# eos26_motherboard_basic.net
KiCad netlist of a schematic drawn in Altium Designer
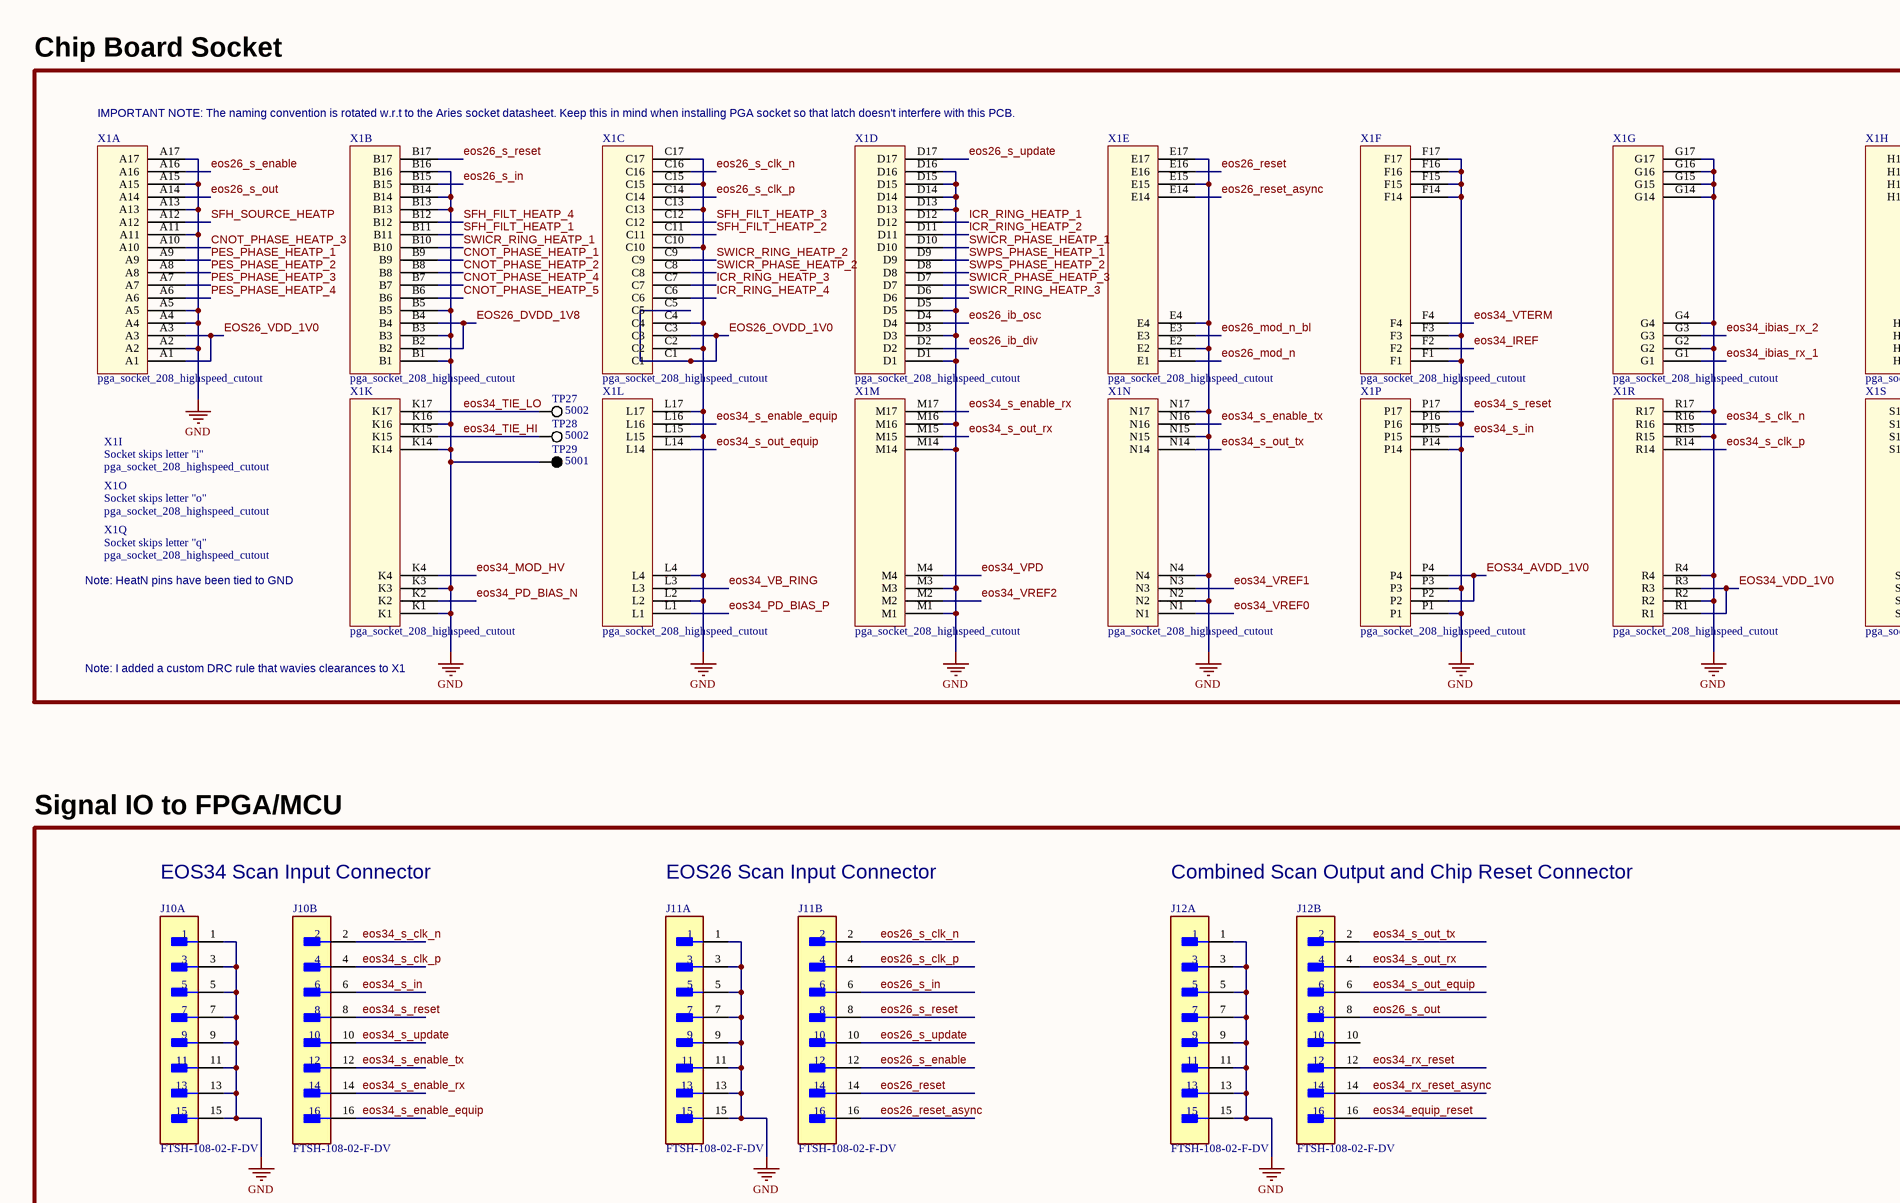
[diagram p0: eos26_motherboard_basic.SchDoc, top left]
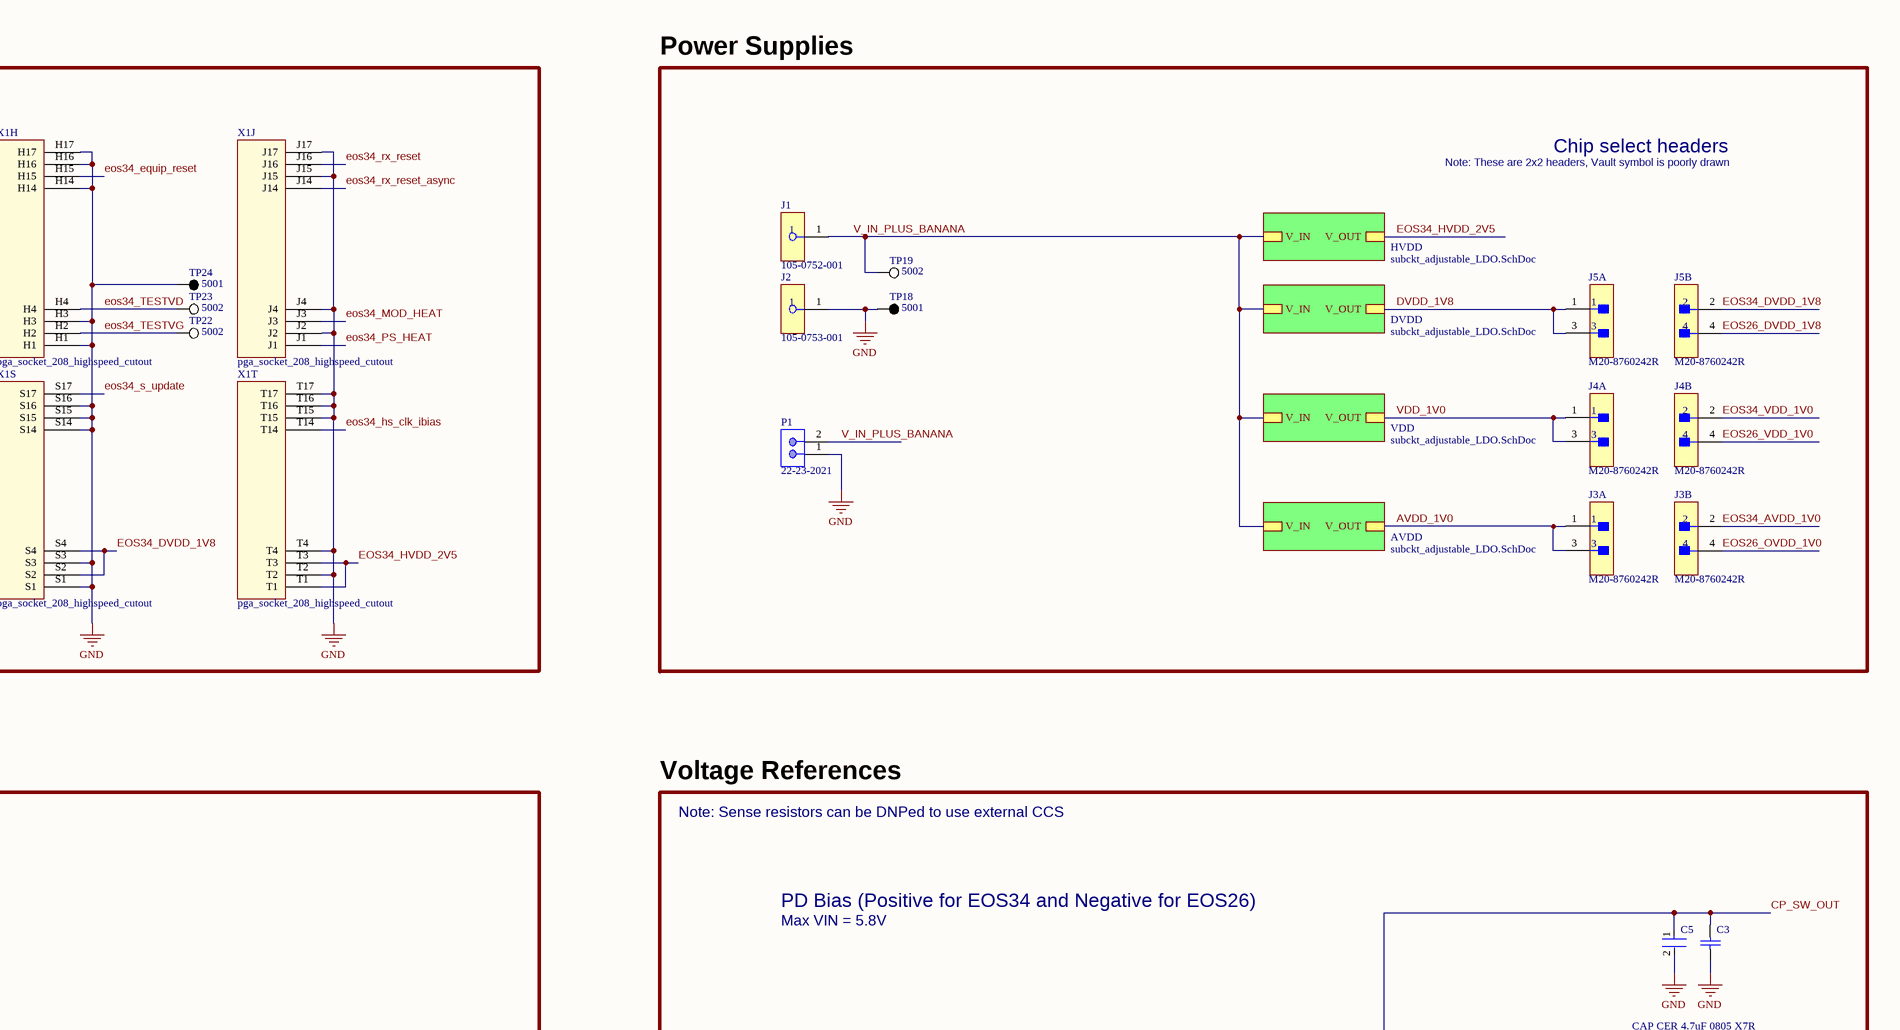
[diagram p1: eos26_motherboard_basic.SchDoc, top right]
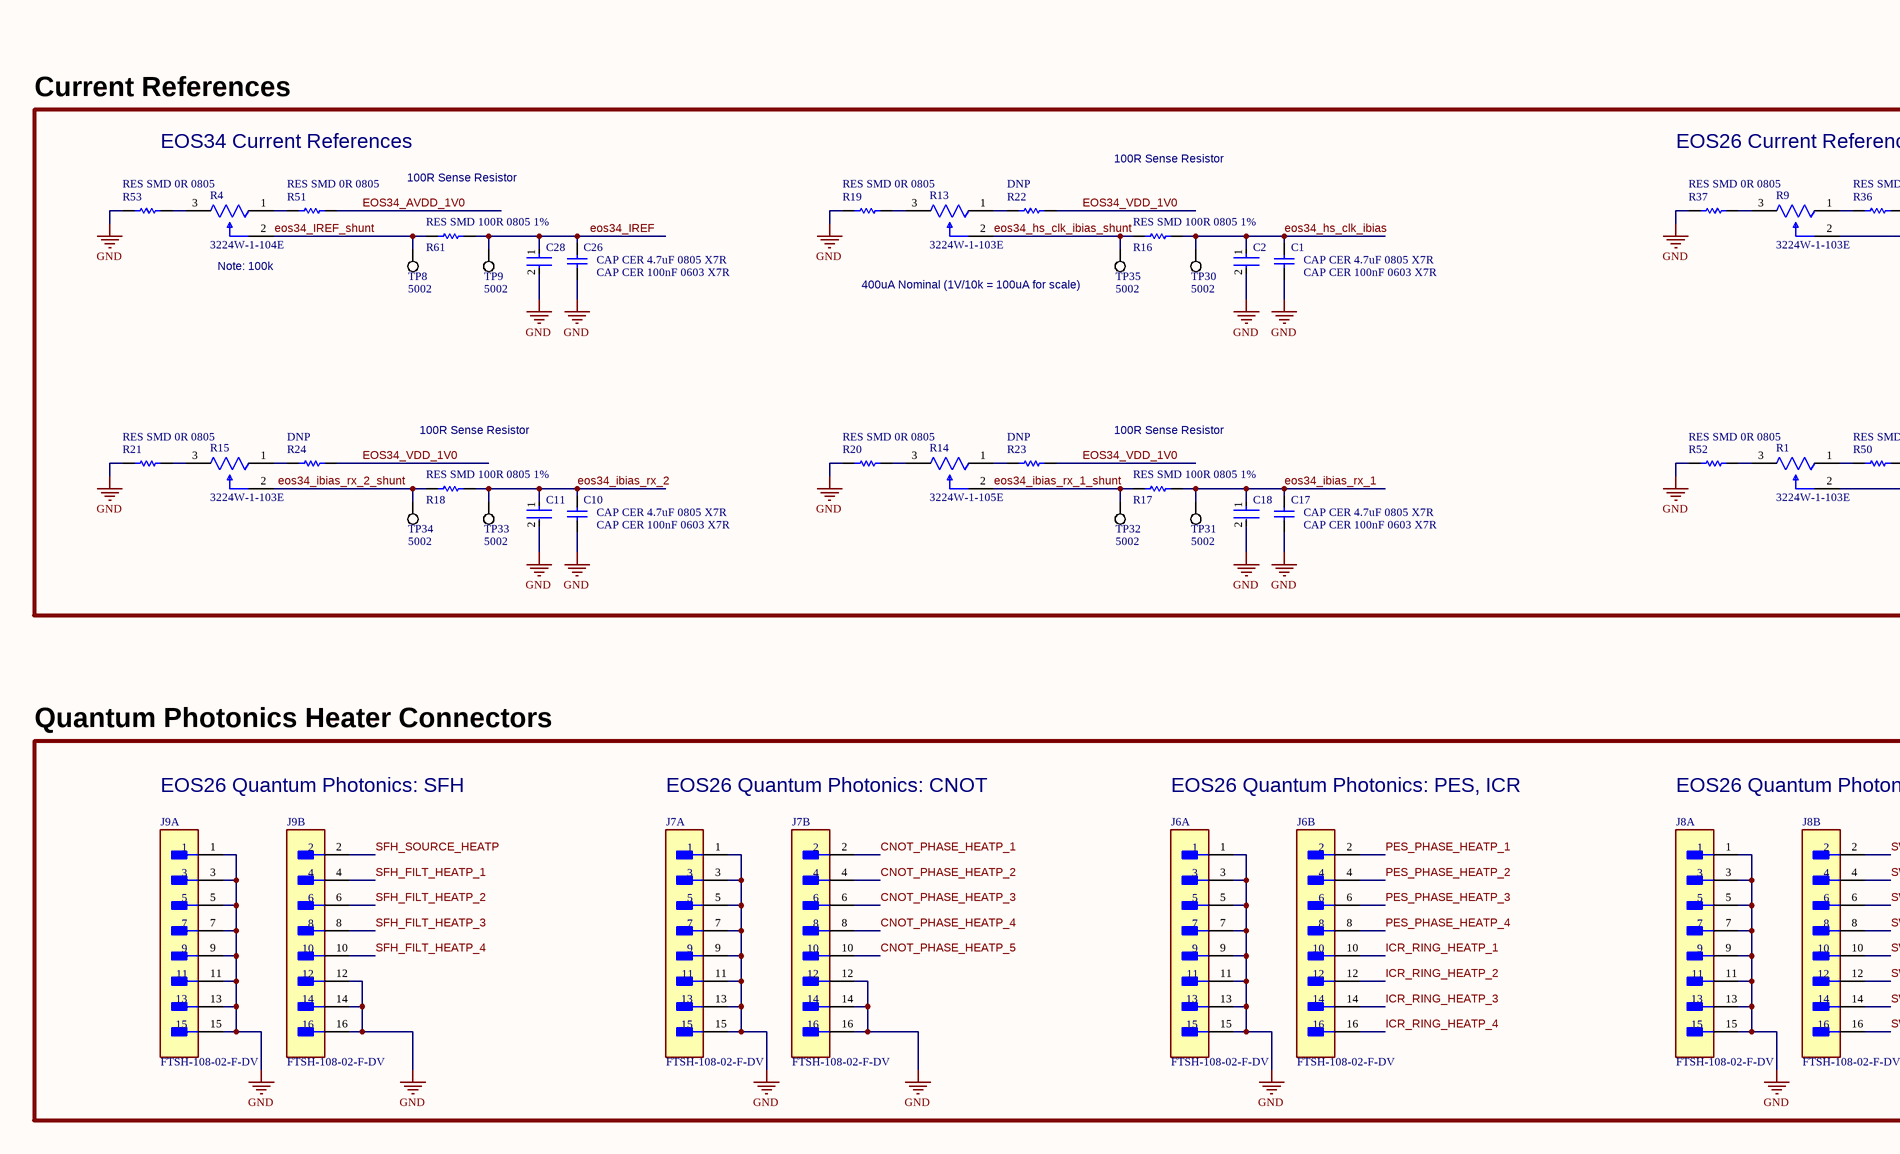
[diagram p2: eos26_motherboard_basic.SchDoc, bottom left]
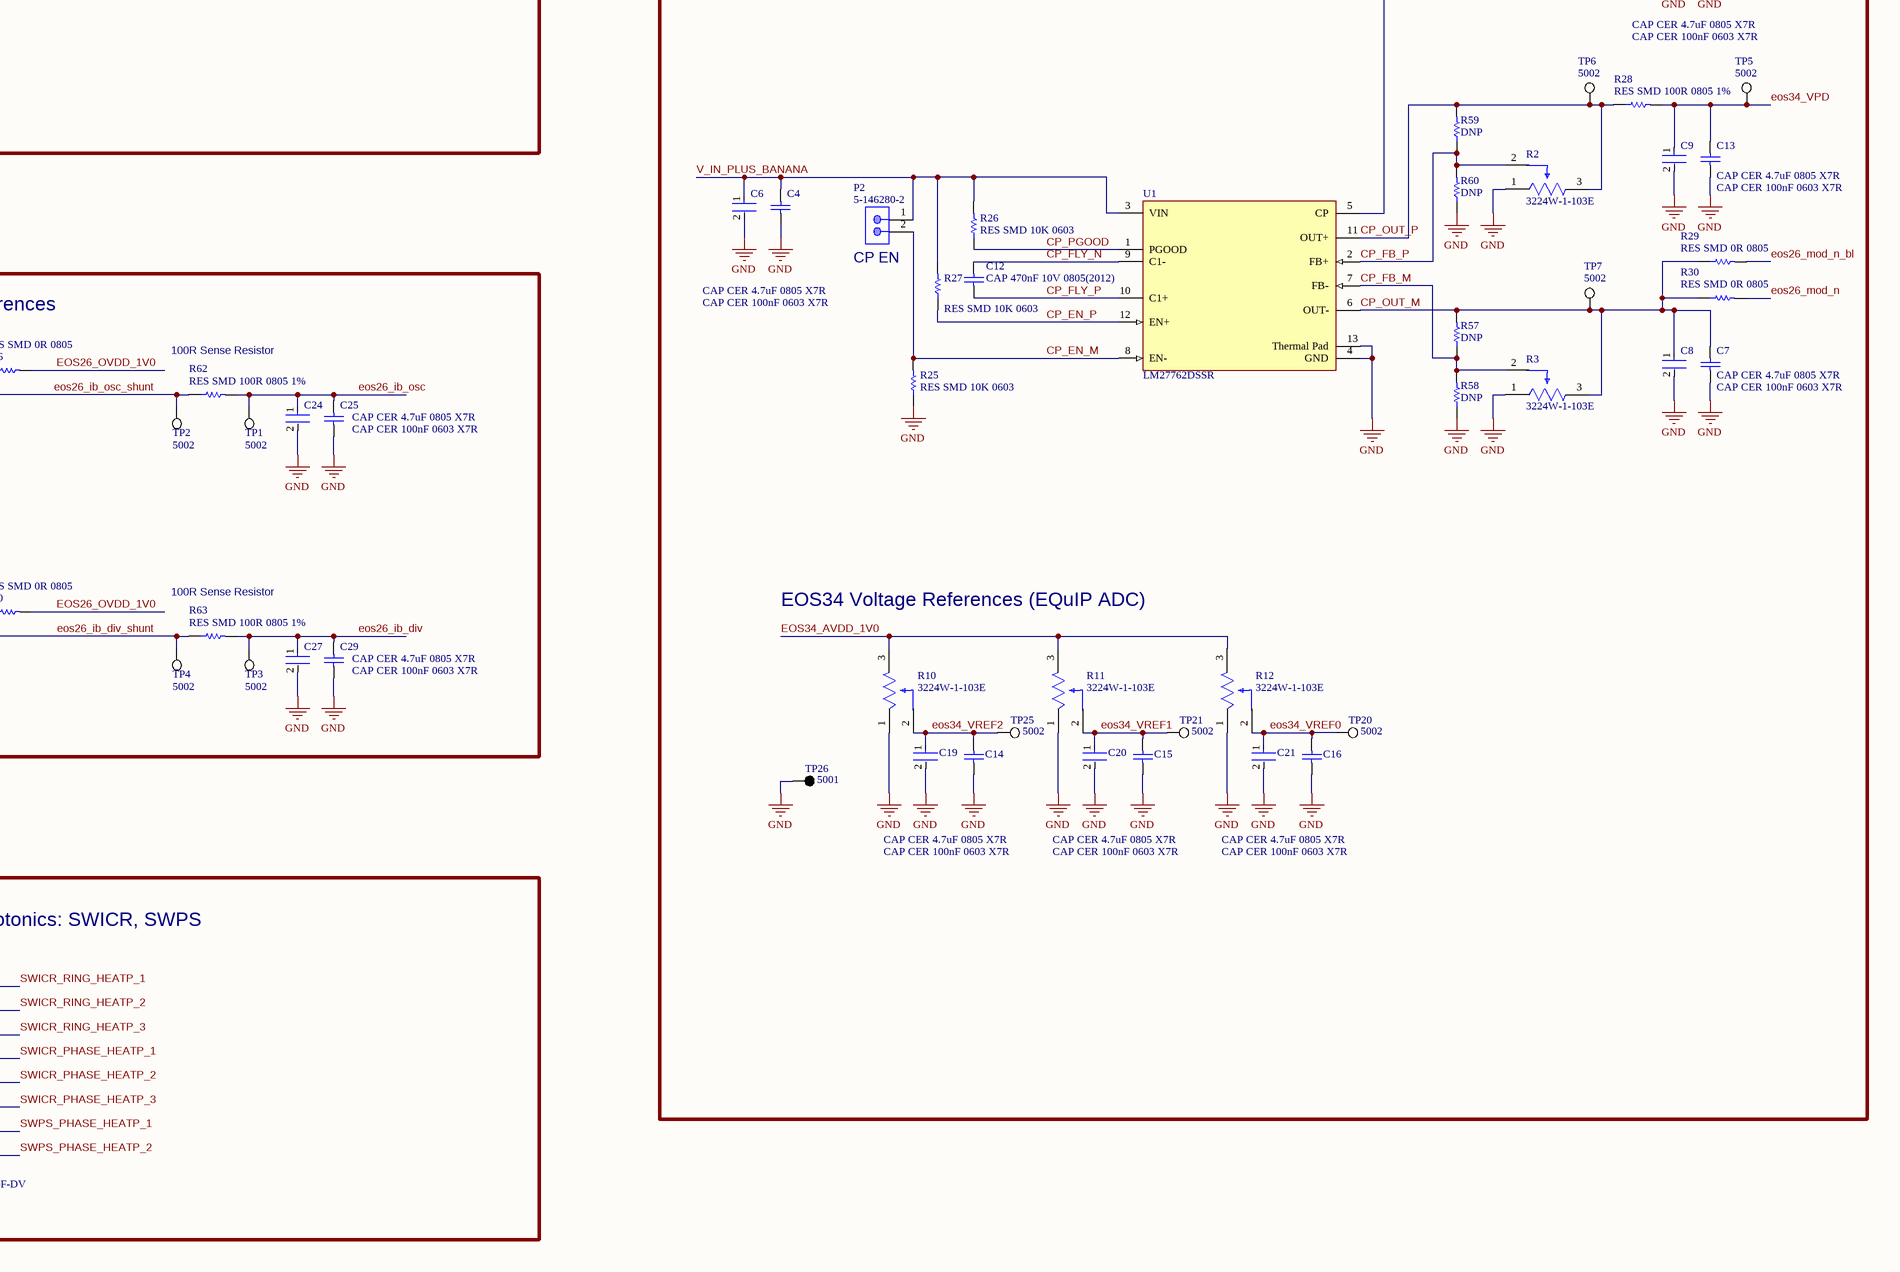
[diagram p3: eos26_motherboard_basic.SchDoc, bottom right]

(export (version "E")
  (design (tool "Eeschema 10.0.6"))
  (components
    (comp (ref "C1")
      (value "CAP CER 4.7uF 0805 X7R")
      (footprint "CAPC2013X140X50NL20T25")
      (fields
        (field (name "PART NUMBER") "0805ZC475KAT2A")
        (field (name "MANUFACTURER") "AVX Interconnect / Elco")
      )
      (libsource (lib "Altium Content Vault") (part "CAP"))
    )
    (comp (ref "C2")
      (value "CAP CER 100nF 0603 X7R")
      (footprint "FP-CC0603-DA-MFG")
      (description "CAP CER 0.1UF 16V X7R 0603")
      (fields
        (field (name "OCTOPART") "https://octopart.com/cc0603krx7r7bb104-yageo-192941")
        (field (name "TOLERANCE") "0.1")
      )
      (libsource (lib "Altium Content Vault") (part "11868f565c42a9108669ba33697ecf6"))
    )
    (comp (ref "C3")
      (value "CAP CER 4.7uF 0805 X7R")
      (footprint "CAPC2013X140X50NL20T25")
      (fields
        (field (name "PART NUMBER") "0805ZC475KAT2A")
        (field (name "MANUFACTURER") "AVX Interconnect / Elco")
      )
      (libsource (lib "Altium Content Vault") (part "CAP"))
    )
    (comp (ref "C4")
      (value "CAP CER 4.7uF 0805 X7R")
      (footprint "CAPC2013X140X50NL20T25")
      (fields
        (field (name "PART NUMBER") "0805ZC475KAT2A")
        (field (name "MANUFACTURER") "AVX Interconnect / Elco")
      )
      (libsource (lib "Altium Content Vault") (part "CAP"))
    )
    (comp (ref "C5")
      (value "CAP CER 100nF 0603 X7R")
      (footprint "FP-CC0603-DA-MFG")
      (description "CAP CER 0.1UF 16V X7R 0603")
      (fields
        (field (name "OCTOPART") "https://octopart.com/cc0603krx7r7bb104-yageo-192941")
        (field (name "TOLERANCE") "0.1")
      )
      (libsource (lib "Altium Content Vault") (part "11868f565c42a9108669ba33697ecf6"))
    )
    (comp (ref "C6")
      (value "CAP CER 100nF 0603 X7R")
      (footprint "FP-CC0603-DA-MFG")
      (description "CAP CER 0.1UF 16V X7R 0603")
      (fields
        (field (name "OCTOPART") "https://octopart.com/cc0603krx7r7bb104-yageo-192941")
        (field (name "TOLERANCE") "0.1")
      )
      (libsource (lib "Altium Content Vault") (part "11868f565c42a9108669ba33697ecf6"))
    )
    (comp (ref "C7")
      (value "CAP CER 4.7uF 0805 X7R")
      (footprint "CAPC2013X140X50NL20T25")
      (fields
        (field (name "PART NUMBER") "0805ZC475KAT2A")
        (field (name "MANUFACTURER") "AVX Interconnect / Elco")
      )
      (libsource (lib "Altium Content Vault") (part "CAP"))
    )
    (comp (ref "C8")
      (value "CAP CER 100nF 0603 X7R")
      (footprint "FP-CC0603-DA-MFG")
      (description "CAP CER 0.1UF 16V X7R 0603")
      (fields
        (field (name "OCTOPART") "https://octopart.com/cc0603krx7r7bb104-yageo-192941")
        (field (name "TOLERANCE") "0.1")
      )
      (libsource (lib "Altium Content Vault") (part "11868f565c42a9108669ba33697ecf6"))
    )
    (comp (ref "C9")
      (value "CAP CER 100nF 0603 X7R")
      (footprint "FP-CC0603-DA-MFG")
      (description "CAP CER 0.1UF 16V X7R 0603")
      (fields
        (field (name "OCTOPART") "https://octopart.com/cc0603krx7r7bb104-yageo-192941")
        (field (name "TOLERANCE") "0.1")
      )
      (libsource (lib "Altium Content Vault") (part "11868f565c42a9108669ba33697ecf6"))
    )
    (comp (ref "C10")
      (value "CAP CER 4.7uF 0805 X7R")
      (footprint "CAPC2013X140X50NL20T25")
      (fields
        (field (name "PART NUMBER") "0805ZC475KAT2A")
        (field (name "MANUFACTURER") "AVX Interconnect / Elco")
      )
      (libsource (lib "Altium Content Vault") (part "CAP"))
    )
    (comp (ref "C11")
      (value "CAP CER 100nF 0603 X7R")
      (footprint "FP-CC0603-DA-MFG")
      (description "CAP CER 0.1UF 16V X7R 0603")
      (fields
        (field (name "OCTOPART") "https://octopart.com/cc0603krx7r7bb104-yageo-192941")
        (field (name "TOLERANCE") "0.1")
      )
      (libsource (lib "Altium Content Vault") (part "11868f565c42a9108669ba33697ecf6"))
    )
    (comp (ref "C12")
      (value "CAP 470nF 10V 0805(2012)")
      (footprint "CAPC0805(2012)145_M")
      (description "CAP 470nF 10V ±5% 0805 (2012 Metric) Thickness 1.45mm SMD")
      (fields (field (name "TOLERANCE") "Â±5%"))
      (libsource (lib "Altium Content Vault") (part "CAP"))
    )
    (comp (ref "C13")
      (value "CAP CER 4.7uF 0805 X7R")
      (footprint "CAPC2013X140X50NL20T25")
      (fields
        (field (name "PART NUMBER") "0805ZC475KAT2A")
        (field (name "MANUFACTURER") "AVX Interconnect / Elco")
      )
      (libsource (lib "Altium Content Vault") (part "CAP"))
    )
    (comp (ref "C14")
      (value "CAP CER 4.7uF 0805 X7R")
      (footprint "CAPC2013X140X50NL20T25")
      (fields
        (field (name "PART NUMBER") "0805ZC475KAT2A")
        (field (name "MANUFACTURER") "AVX Interconnect / Elco")
      )
      (libsource (lib "Altium Content Vault") (part "CAP"))
    )
    (comp (ref "C15")
      (value "CAP CER 4.7uF 0805 X7R")
      (footprint "CAPC2013X140X50NL20T25")
      (fields
        (field (name "PART NUMBER") "0805ZC475KAT2A")
        (field (name "MANUFACTURER") "AVX Interconnect / Elco")
      )
      (libsource (lib "Altium Content Vault") (part "CAP"))
    )
    (comp (ref "C16")
      (value "CAP CER 4.7uF 0805 X7R")
      (footprint "CAPC2013X140X50NL20T25")
      (fields
        (field (name "PART NUMBER") "0805ZC475KAT2A")
        (field (name "MANUFACTURER") "AVX Interconnect / Elco")
      )
      (libsource (lib "Altium Content Vault") (part "CAP"))
    )
    (comp (ref "C17")
      (value "CAP CER 4.7uF 0805 X7R")
      (footprint "CAPC2013X140X50NL20T25")
      (fields
        (field (name "PART NUMBER") "0805ZC475KAT2A")
        (field (name "MANUFACTURER") "AVX Interconnect / Elco")
      )
      (libsource (lib "Altium Content Vault") (part "CAP"))
    )
    (comp (ref "C18")
      (value "CAP CER 100nF 0603 X7R")
      (footprint "FP-CC0603-DA-MFG")
      (description "CAP CER 0.1UF 16V X7R 0603")
      (fields
        (field (name "OCTOPART") "https://octopart.com/cc0603krx7r7bb104-yageo-192941")
        (field (name "TOLERANCE") "0.1")
      )
      (libsource (lib "Altium Content Vault") (part "11868f565c42a9108669ba33697ecf6"))
    )
    (comp (ref "C19")
      (value "CAP CER 100nF 0603 X7R")
      (footprint "FP-CC0603-DA-MFG")
      (description "CAP CER 0.1UF 16V X7R 0603")
      (fields
        (field (name "OCTOPART") "https://octopart.com/cc0603krx7r7bb104-yageo-192941")
        (field (name "TOLERANCE") "0.1")
      )
      (libsource (lib "Altium Content Vault") (part "11868f565c42a9108669ba33697ecf6"))
    )
    (comp (ref "C20")
      (value "CAP CER 100nF 0603 X7R")
      (footprint "FP-CC0603-DA-MFG")
      (description "CAP CER 0.1UF 16V X7R 0603")
      (fields
        (field (name "OCTOPART") "https://octopart.com/cc0603krx7r7bb104-yageo-192941")
        (field (name "TOLERANCE") "0.1")
      )
      (libsource (lib "Altium Content Vault") (part "11868f565c42a9108669ba33697ecf6"))
    )
    (comp (ref "C21")
      (value "CAP CER 100nF 0603 X7R")
      (footprint "FP-CC0603-DA-MFG")
      (description "CAP CER 0.1UF 16V X7R 0603")
      (fields
        (field (name "OCTOPART") "https://octopart.com/cc0603krx7r7bb104-yageo-192941")
        (field (name "TOLERANCE") "0.1")
      )
      (libsource (lib "Altium Content Vault") (part "11868f565c42a9108669ba33697ecf6"))
    )
    (comp (ref "C24")
      (value "CAP CER 100nF 0603 X7R")
      (footprint "FP-CC0603-DA-MFG")
      (description "CAP CER 0.1UF 16V X7R 0603")
      (fields
        (field (name "OCTOPART") "https://octopart.com/cc0603krx7r7bb104-yageo-192941")
        (field (name "TOLERANCE") "0.1")
      )
      (libsource (lib "Altium Content Vault") (part "11868f565c42a9108669ba33697ecf6"))
    )
    (comp (ref "C25")
      (value "CAP CER 4.7uF 0805 X7R")
      (footprint "CAPC2013X140X50NL20T25")
      (fields
        (field (name "PART NUMBER") "0805ZC475KAT2A")
        (field (name "MANUFACTURER") "AVX Interconnect / Elco")
      )
      (libsource (lib "Altium Content Vault") (part "CAP"))
    )
    (comp (ref "C26")
      (value "CAP CER 4.7uF 0805 X7R")
      (footprint "CAPC2013X140X50NL20T25")
      (fields
        (field (name "PART NUMBER") "0805ZC475KAT2A")
        (field (name "MANUFACTURER") "AVX Interconnect / Elco")
      )
      (libsource (lib "Altium Content Vault") (part "CAP"))
    )
    (comp (ref "C27")
      (value "CAP CER 100nF 0603 X7R")
      (footprint "FP-CC0603-DA-MFG")
      (description "CAP CER 0.1UF 16V X7R 0603")
      (fields
        (field (name "OCTOPART") "https://octopart.com/cc0603krx7r7bb104-yageo-192941")
        (field (name "TOLERANCE") "0.1")
      )
      (libsource (lib "Altium Content Vault") (part "11868f565c42a9108669ba33697ecf6"))
    )
    (comp (ref "C28")
      (value "CAP CER 100nF 0603 X7R")
      (footprint "FP-CC0603-DA-MFG")
      (description "CAP CER 0.1UF 16V X7R 0603")
      (fields
        (field (name "OCTOPART") "https://octopart.com/cc0603krx7r7bb104-yageo-192941")
        (field (name "TOLERANCE") "0.1")
      )
      (libsource (lib "Altium Content Vault") (part "11868f565c42a9108669ba33697ecf6"))
    )
    (comp (ref "C29")
      (value "CAP CER 4.7uF 0805 X7R")
      (footprint "CAPC2013X140X50NL20T25")
      (fields
        (field (name "PART NUMBER") "0805ZC475KAT2A")
        (field (name "MANUFACTURER") "AVX Interconnect / Elco")
      )
      (libsource (lib "Altium Content Vault") (part "CAP"))
    )
    (comp (ref "J1")
      (value "105-0752-001")
      (footprint "FP-105-0751-001-MFG")
      (description "CONN TIP JACK SOLDER WHITE")
      (fields
        (field (name "MANUFACTURER") "Cinch Connectivity")
        (field (name "OCTOPART") "https://octopart.com/105-0751-001-cinch+connectivity+solutions-51372833")
      )
      (libsource (lib "Altium Content Vault") (part "98815daf2f2c152b0c43f5ab9800df6"))
    )
    (comp (ref "J2")
      (value "105-0753-001")
      (footprint "FP-105-0751-001-MFG")
      (description "CONN TIP JACK SOLDER WHITE")
      (fields
        (field (name "MANUFACTURER") "Cinch Connectivity")
        (field (name "OCTOPART") "https://octopart.com/105-0751-001-cinch+connectivity+solutions-51372833")
      )
      (libsource (lib "Altium Content Vault") (part "98815daf2f2c152b0c43f5ab9800df6"))
    )
    (comp (ref "J3")
      (value "M20-8760242R")
      (footprint "FP-M20-8760242R-MFG")
      (description "CONN HEADER SMD 4POS 2.54MM")
      (libsource (lib "Altium Content Vault") (part "1621473add15499e993d6bbd36d0f06"))
    )
    (comp (ref "J4")
      (value "M20-8760242R")
      (footprint "FP-M20-8760242R-MFG")
      (description "CONN HEADER SMD 4POS 2.54MM")
      (libsource (lib "Altium Content Vault") (part "1621473add15499e993d6bbd36d0f06"))
    )
    (comp (ref "J5")
      (value "M20-8760242R")
      (footprint "FP-M20-8760242R-MFG")
      (description "CONN HEADER SMD 4POS 2.54MM")
      (libsource (lib "Altium Content Vault") (part "1621473add15499e993d6bbd36d0f06"))
    )
    (comp (ref "J6")
      (value "FTSH-108-02-F-DV")
      (footprint "LIBRARYSOURCE=Vault¦VAULTGUID=B7D15EC3-160A-466F-A46C-7801FE6295A7¦REVISIONGUID=4386816A-B426-492F-A73C-09950B70C106¦FOOTPRINT=FP-FTSH-108-02-F-DV")
      (description "CONN HEADER SMD 16POS 1.27MM")
      (fields
        (field (name "OCTOPART") "https://octopart.com/ftsh-108-02-f-dv-samtec-10605893")
        (field (name "MANUFACTURER") "Samtec")
      )
      (libsource (lib "SMT_header_FTSH") (part "FP-FTSH-108-02-F-DV"))
    )
    (comp (ref "J7")
      (value "FTSH-108-02-F-DV")
      (footprint "LIBRARYSOURCE=Vault¦VAULTGUID=B7D15EC3-160A-466F-A46C-7801FE6295A7¦REVISIONGUID=4386816A-B426-492F-A73C-09950B70C106¦FOOTPRINT=FP-FTSH-108-02-F-DV")
      (description "CONN HEADER SMD 16POS 1.27MM")
      (fields
        (field (name "OCTOPART") "https://octopart.com/ftsh-108-02-f-dv-samtec-10605893")
        (field (name "MANUFACTURER") "Samtec")
      )
      (libsource (lib "SMT_header_FTSH") (part "FP-FTSH-108-02-F-DV"))
    )
    (comp (ref "J8")
      (value "FTSH-108-02-F-DV")
      (footprint "LIBRARYSOURCE=Vault¦VAULTGUID=B7D15EC3-160A-466F-A46C-7801FE6295A7¦REVISIONGUID=4386816A-B426-492F-A73C-09950B70C106¦FOOTPRINT=FP-FTSH-108-02-F-DV")
      (description "CONN HEADER SMD 16POS 1.27MM")
      (fields
        (field (name "OCTOPART") "https://octopart.com/ftsh-108-02-f-dv-samtec-10605893")
        (field (name "MANUFACTURER") "Samtec")
      )
      (libsource (lib "SMT_header_FTSH") (part "FP-FTSH-108-02-F-DV"))
    )
    (comp (ref "J9")
      (value "FTSH-108-02-F-DV")
      (footprint "LIBRARYSOURCE=Vault¦VAULTGUID=B7D15EC3-160A-466F-A46C-7801FE6295A7¦REVISIONGUID=4386816A-B426-492F-A73C-09950B70C106¦FOOTPRINT=FP-FTSH-108-02-F-DV")
      (description "CONN HEADER SMD 16POS 1.27MM")
      (fields
        (field (name "OCTOPART") "https://octopart.com/ftsh-108-02-f-dv-samtec-10605893")
        (field (name "MANUFACTURER") "Samtec")
      )
      (libsource (lib "SMT_header_FTSH") (part "FP-FTSH-108-02-F-DV"))
    )
    (comp (ref "J10")
      (value "FTSH-108-02-F-DV")
      (footprint "LIBRARYSOURCE=Vault¦VAULTGUID=B7D15EC3-160A-466F-A46C-7801FE6295A7¦REVISIONGUID=4386816A-B426-492F-A73C-09950B70C106¦FOOTPRINT=FP-FTSH-108-02-F-DV")
      (description "CONN HEADER SMD 16POS 1.27MM")
      (fields
        (field (name "OCTOPART") "https://octopart.com/ftsh-108-02-f-dv-samtec-10605893")
        (field (name "MANUFACTURER") "Samtec")
      )
      (libsource (lib "SMT_header_FTSH") (part "FP-FTSH-108-02-F-DV"))
    )
    (comp (ref "J11")
      (value "FTSH-108-02-F-DV")
      (footprint "LIBRARYSOURCE=Vault¦VAULTGUID=B7D15EC3-160A-466F-A46C-7801FE6295A7¦REVISIONGUID=4386816A-B426-492F-A73C-09950B70C106¦FOOTPRINT=FP-FTSH-108-02-F-DV")
      (description "CONN HEADER SMD 16POS 1.27MM")
      (fields
        (field (name "OCTOPART") "https://octopart.com/ftsh-108-02-f-dv-samtec-10605893")
        (field (name "MANUFACTURER") "Samtec")
      )
      (libsource (lib "SMT_header_FTSH") (part "FP-FTSH-108-02-F-DV"))
    )
    (comp (ref "J12")
      (value "FTSH-108-02-F-DV")
      (footprint "LIBRARYSOURCE=Vault¦VAULTGUID=B7D15EC3-160A-466F-A46C-7801FE6295A7¦REVISIONGUID=4386816A-B426-492F-A73C-09950B70C106¦FOOTPRINT=FP-FTSH-108-02-F-DV")
      (description "CONN HEADER SMD 16POS 1.27MM")
      (fields
        (field (name "OCTOPART") "https://octopart.com/ftsh-108-02-f-dv-samtec-10605893")
        (field (name "MANUFACTURER") "Samtec")
      )
      (libsource (lib "SMT_header_FTSH") (part "FP-FTSH-108-02-F-DV"))
    )
    (comp (ref "P1")
      (value "22-23-2021")
      (footprint "MOLX-22-23-2021_V")
      (libsource (lib "Altium Content Vault") (part "CN-1P-M-R2"))
    )
    (comp (ref "P2")
      (value "5-146280-2")
      (footprint "TECO-5-146280-2_V")
      (fields (field (name "MANUFACTURER") "TE Connectivity"))
      (libsource (lib "") (part "CN-1P-M-R2_1"))
    )
    (comp (ref "R1")
      (value "3224W-1-103E")
      (footprint "FP-3224W-MFG")
      (description "TRIMMER 10K OHM 0.25W J LEAD TOP")
      (fields (field (name "TOLERANCE") "10%") (field (name "MANUFACTURER") "Bourns"))
      (libsource (lib "Altium Content Vault") (part "83d3d349ed884d1db45cec512f27eb6"))
    )
    (comp (ref "R2")
      (value "3224W-1-103E")
      (footprint "FP-3224W-MFG")
      (description "TRIMMER 10K OHM 0.25W J LEAD TOP")
      (fields (field (name "TOLERANCE") "10%") (field (name "MANUFACTURER") "Bourns"))
      (libsource (lib "Altium Content Vault") (part "83d3d349ed884d1db45cec512f27eb6"))
    )
    (comp (ref "R3")
      (value "3224W-1-103E")
      (footprint "FP-3224W-MFG")
      (description "TRIMMER 10K OHM 0.25W J LEAD TOP")
      (fields (field (name "TOLERANCE") "10%") (field (name "MANUFACTURER") "Bourns"))
      (libsource (lib "Altium Content Vault") (part "83d3d349ed884d1db45cec512f27eb6"))
    )
    (comp (ref "R4")
      (value "3224W-1-104E")
      (footprint "FP-3224W-MFG")
      (description "TRIMMER 10K OHM 0.25W J LEAD TOP")
      (fields (field (name "TOLERANCE") "10%") (field (name "MANUFACTURER") "Bourns"))
      (libsource (lib "Altium Content Vault") (part "83d3d349ed884d1db45cec512f27eb6"))
    )
    (comp (ref "R9")
      (value "3224W-1-103E")
      (footprint "FP-3224W-MFG")
      (description "TRIMMER 10K OHM 0.25W J LEAD TOP")
      (fields (field (name "TOLERANCE") "10%") (field (name "MANUFACTURER") "Bourns"))
      (libsource (lib "Altium Content Vault") (part "83d3d349ed884d1db45cec512f27eb6"))
    )
    (comp (ref "R10")
      (value "3224W-1-103E")
      (footprint "FP-3224W-MFG")
      (description "TRIMMER 10K OHM 0.25W J LEAD TOP")
      (fields (field (name "TOLERANCE") "10%") (field (name "MANUFACTURER") "Bourns"))
      (libsource (lib "Altium Content Vault") (part "83d3d349ed884d1db45cec512f27eb6"))
    )
    (comp (ref "R11")
      (value "3224W-1-103E")
      (footprint "FP-3224W-MFG")
      (description "TRIMMER 10K OHM 0.25W J LEAD TOP")
      (fields (field (name "TOLERANCE") "10%") (field (name "MANUFACTURER") "Bourns"))
      (libsource (lib "Altium Content Vault") (part "83d3d349ed884d1db45cec512f27eb6"))
    )
    (comp (ref "R12")
      (value "3224W-1-103E")
      (footprint "FP-3224W-MFG")
      (description "TRIMMER 10K OHM 0.25W J LEAD TOP")
      (fields (field (name "TOLERANCE") "10%") (field (name "MANUFACTURER") "Bourns"))
      (libsource (lib "Altium Content Vault") (part "83d3d349ed884d1db45cec512f27eb6"))
    )
    (comp (ref "R13")
      (value "3224W-1-103E")
      (footprint "FP-3224W-MFG")
      (description "TRIMMER 10K OHM 0.25W J LEAD TOP")
      (fields (field (name "TOLERANCE") "10%") (field (name "MANUFACTURER") "Bourns"))
      (libsource (lib "Altium Content Vault") (part "83d3d349ed884d1db45cec512f27eb6"))
    )
    (comp (ref "R14")
      (value "3224W-1-105E")
      (footprint "FP-3224W-MFG")
      (description "TRIMMER 10K OHM 0.25W J LEAD TOP")
      (fields (field (name "TOLERANCE") "10%") (field (name "MANUFACTURER") "Bourns"))
      (libsource (lib "Altium Content Vault") (part "83d3d349ed884d1db45cec512f27eb6"))
    )
    (comp (ref "R15")
      (value "3224W-1-103E")
      (footprint "FP-3224W-MFG")
      (description "TRIMMER 10K OHM 0.25W J LEAD TOP")
      (fields (field (name "TOLERANCE") "10%") (field (name "MANUFACTURER") "Bourns"))
      (libsource (lib "Altium Content Vault") (part "83d3d349ed884d1db45cec512f27eb6"))
    )
    (comp (ref "R16")
      (value "RES SMD 100R 0805 1%")
      (footprint "RESC2013X55X40NL15T20")
      (fields (field (name "MANUFACTURER") "Vishay Dale") (field (name "PART NUMBER") "TNPW0805100RBEEA"))
      (libsource (lib "Altium Content Vault") (part "RES"))
    )
    (comp (ref "R17")
      (value "RES SMD 100R 0805 1%")
      (footprint "RESC2013X55X40NL15T20")
      (fields (field (name "MANUFACTURER") "Vishay Dale") (field (name "PART NUMBER") "TNPW0805100RBEEA"))
      (libsource (lib "Altium Content Vault") (part "RES"))
    )
    (comp (ref "R18")
      (value "RES SMD 100R 0805 1%")
      (footprint "RESC2013X55X40NL15T20")
      (fields (field (name "MANUFACTURER") "Vishay Dale") (field (name "PART NUMBER") "TNPW0805100RBEEA"))
      (libsource (lib "Altium Content Vault") (part "RES"))
    )
    (comp (ref "R19")
      (value "RES SMD 0R 0805")
      (footprint "RESC2013X55X40NL15T20")
      (fields (field (name "MANUFACTURER") "Vishay Dale") (field (name "PART NUMBER") "TNPW0805100RBEEA"))
      (libsource (lib "Altium Content Vault") (part "RES"))
    )
    (comp (ref "R20")
      (value "RES SMD 0R 0805")
      (footprint "RESC2013X55X40NL15T20")
      (fields (field (name "MANUFACTURER") "Vishay Dale") (field (name "PART NUMBER") "TNPW0805100RBEEA"))
      (libsource (lib "Altium Content Vault") (part "RES"))
    )
    (comp (ref "R21")
      (value "RES SMD 0R 0805")
      (footprint "RESC2013X55X40NL15T20")
      (fields (field (name "MANUFACTURER") "Vishay Dale") (field (name "PART NUMBER") "TNPW0805100RBEEA"))
      (libsource (lib "Altium Content Vault") (part "RES"))
    )
    (comp (ref "R22")
      (value "DNP")
      (footprint "RESC2013X55X40NL15T20")
      (fields (field (name "MANUFACTURER") "Vishay Dale") (field (name "PART NUMBER") "TNPW0805100RBEEA"))
      (libsource (lib "Altium Content Vault") (part "RES"))
    )
    (comp (ref "R23")
      (value "DNP")
      (footprint "RESC2013X55X40NL15T20")
      (fields (field (name "MANUFACTURER") "Vishay Dale") (field (name "PART NUMBER") "TNPW0805100RBEEA"))
      (libsource (lib "Altium Content Vault") (part "RES"))
    )
    (comp (ref "R24")
      (value "DNP")
      (footprint "RESC2013X55X40NL15T20")
      (fields (field (name "MANUFACTURER") "Vishay Dale") (field (name "PART NUMBER") "TNPW0805100RBEEA"))
      (libsource (lib "Altium Content Vault") (part "RES"))
    )
    (comp (ref "R25")
      (value "RES SMD 10K 0603")
      (footprint "RESC1609X55X30LL15T15")
      (description "Chip Resistor, 10 KOhm, +/- 1%, 0.1 W, -55 to 155 degC, 0603 (1608 Metric), RoHS, Tape and Reel")
      (fields (field (name "TOLERANCE") "1%") (field (name "MANUFACTURER") "Panasonic"))
      (libsource (lib "Altium Content Vault") (part "RES-2"))
    )
    (comp (ref "R26")
      (value "RES SMD 10K 0603")
      (footprint "RESC1609X55X30LL15T15")
      (description "Chip Resistor, 10 KOhm, +/- 1%, 0.1 W, -55 to 155 degC, 0603 (1608 Metric), RoHS, Tape and Reel")
      (fields (field (name "TOLERANCE") "1%") (field (name "MANUFACTURER") "Panasonic"))
      (libsource (lib "Altium Content Vault") (part "RES-2"))
    )
    (comp (ref "R27")
      (value "RES SMD 10K 0603")
      (footprint "RESC1609X55X30LL15T15")
      (description "Chip Resistor, 10 KOhm, +/- 1%, 0.1 W, -55 to 155 degC, 0603 (1608 Metric), RoHS, Tape and Reel")
      (fields (field (name "TOLERANCE") "1%") (field (name "MANUFACTURER") "Panasonic"))
      (libsource (lib "Altium Content Vault") (part "RES-2"))
    )
    (comp (ref "R28")
      (value "RES SMD 100R 0805 1%")
      (footprint "RESC2013X55X40NL15T20")
      (fields (field (name "MANUFACTURER") "Vishay Dale") (field (name "PART NUMBER") "TNPW0805100RBEEA"))
      (libsource (lib "Altium Content Vault") (part "RES"))
    )
    (comp (ref "R29")
      (value "RES SMD 0R 0805")
      (footprint "RESC2013X55X40NL15T20")
      (fields (field (name "MANUFACTURER") "Vishay Dale") (field (name "PART NUMBER") "TNPW0805100RBEEA"))
      (libsource (lib "Altium Content Vault") (part "RES"))
    )
    (comp (ref "R30")
      (value "RES SMD 0R 0805")
      (footprint "RESC2013X55X40NL15T20")
      (fields (field (name "MANUFACTURER") "Vishay Dale") (field (name "PART NUMBER") "TNPW0805100RBEEA"))
      (libsource (lib "Altium Content Vault") (part "RES"))
    )
    (comp (ref "R36")
      (value "RES SMD 0R 0805")
      (footprint "RESC2013X55X40NL15T20")
      (fields (field (name "MANUFACTURER") "Vishay Dale") (field (name "PART NUMBER") "TNPW0805100RBEEA"))
      (libsource (lib "Altium Content Vault") (part "RES"))
    )
    (comp (ref "R37")
      (value "RES SMD 0R 0805")
      (footprint "RESC2013X55X40NL15T20")
      (fields (field (name "MANUFACTURER") "Vishay Dale") (field (name "PART NUMBER") "TNPW0805100RBEEA"))
      (libsource (lib "Altium Content Vault") (part "RES"))
    )
    (comp (ref "R50")
      (value "RES SMD 0R 0805")
      (footprint "RESC2013X55X40NL15T20")
      (fields (field (name "MANUFACTURER") "Vishay Dale") (field (name "PART NUMBER") "TNPW0805100RBEEA"))
      (libsource (lib "Altium Content Vault") (part "RES"))
    )
    (comp (ref "R51")
      (value "RES SMD 0R 0805")
      (footprint "RESC2013X55X40NL15T20")
      (fields (field (name "MANUFACTURER") "Vishay Dale") (field (name "PART NUMBER") "TNPW0805100RBEEA"))
      (libsource (lib "Altium Content Vault") (part "RES"))
    )
    (comp (ref "R52")
      (value "RES SMD 0R 0805")
      (footprint "RESC2013X55X40NL15T20")
      (fields (field (name "MANUFACTURER") "Vishay Dale") (field (name "PART NUMBER") "TNPW0805100RBEEA"))
      (libsource (lib "Altium Content Vault") (part "RES"))
    )
    (comp (ref "R53")
      (value "RES SMD 0R 0805")
      (footprint "RESC2013X55X40NL15T20")
      (fields (field (name "MANUFACTURER") "Vishay Dale") (field (name "PART NUMBER") "TNPW0805100RBEEA"))
      (libsource (lib "Altium Content Vault") (part "RES"))
    )
    (comp (ref "R57")
      (value "DNP")
      (footprint "RESC1608X55X30LL10T20_A")
      (description "Chip Resistor, 0 Ohm, +/- 5%, 100 mW, -55 to 155 degC, 0603 (1608 Metric), RoHS, Tape and Reel")
      (fields (field (name "TOLERANCE") "Jumper") (field (name "MANUFACTURER") "Rohm"))
      (libsource (lib "Altium Content Vault") (part "RES-2"))
    )
    (comp (ref "R58")
      (value "DNP")
      (footprint "RESC1608X55X30LL10T20_A")
      (description "Chip Resistor, 0 Ohm, +/- 5%, 100 mW, -55 to 155 degC, 0603 (1608 Metric), RoHS, Tape and Reel")
      (fields (field (name "TOLERANCE") "Jumper") (field (name "MANUFACTURER") "Rohm"))
      (libsource (lib "Altium Content Vault") (part "RES-2"))
    )
    (comp (ref "R59")
      (value "DNP")
      (footprint "RESC1608X55X30LL10T20_A")
      (description "Chip Resistor, 0 Ohm, +/- 5%, 100 mW, -55 to 155 degC, 0603 (1608 Metric), RoHS, Tape and Reel")
      (fields (field (name "TOLERANCE") "Jumper") (field (name "MANUFACTURER") "Rohm"))
      (libsource (lib "Altium Content Vault") (part "RES-2"))
    )
    (comp (ref "R60")
      (value "DNP")
      (footprint "RESC1608X55X30LL10T20_A")
      (description "Chip Resistor, 0 Ohm, +/- 5%, 100 mW, -55 to 155 degC, 0603 (1608 Metric), RoHS, Tape and Reel")
      (fields (field (name "TOLERANCE") "Jumper") (field (name "MANUFACTURER") "Rohm"))
      (libsource (lib "Altium Content Vault") (part "RES-2"))
    )
    (comp (ref "R61")
      (value "RES SMD 100R 0805 1%")
      (footprint "RESC2013X55X40NL15T20")
      (fields (field (name "MANUFACTURER") "Vishay Dale") (field (name "PART NUMBER") "TNPW0805100RBEEA"))
      (libsource (lib "Altium Content Vault") (part "RES"))
    )
    (comp (ref "R62")
      (value "RES SMD 100R 0805 1%")
      (footprint "RESC2013X55X40NL15T20")
      (fields (field (name "MANUFACTURER") "Vishay Dale") (field (name "PART NUMBER") "TNPW0805100RBEEA"))
      (libsource (lib "Altium Content Vault") (part "RES"))
    )
    (comp (ref "R63")
      (value "RES SMD 100R 0805 1%")
      (footprint "RESC2013X55X40NL15T20")
      (fields (field (name "MANUFACTURER") "Vishay Dale") (field (name "PART NUMBER") "TNPW0805100RBEEA"))
      (libsource (lib "Altium Content Vault") (part "RES"))
    )
    (comp (ref "TP1")
      (value "5002")
      (footprint "KSTN-5002")
      (description "Test Point, White, 1-Pin THD, RoHS, Bulk")
      (fields (field (name "MANUFACTURER") "KeystoneElectronics"))
      (libsource (lib "Altium Content Vault") (part "KSTN-TP-5002"))
    )
    (comp (ref "TP2")
      (value "5002")
      (footprint "KSTN-5002")
      (description "Test Point, White, 1-Pin THD, RoHS, Bulk")
      (fields (field (name "MANUFACTURER") "KeystoneElectronics"))
      (libsource (lib "Altium Content Vault") (part "KSTN-TP-5002"))
    )
    (comp (ref "TP3")
      (value "5002")
      (footprint "KSTN-5002")
      (description "Test Point, White, 1-Pin THD, RoHS, Bulk")
      (fields (field (name "MANUFACTURER") "KeystoneElectronics"))
      (libsource (lib "Altium Content Vault") (part "KSTN-TP-5002"))
    )
    (comp (ref "TP4")
      (value "5002")
      (footprint "KSTN-5002")
      (description "Test Point, White, 1-Pin THD, RoHS, Bulk")
      (fields (field (name "MANUFACTURER") "KeystoneElectronics"))
      (libsource (lib "Altium Content Vault") (part "KSTN-TP-5002"))
    )
    (comp (ref "TP5")
      (value "5002")
      (footprint "KSTN-5002")
      (description "Test Point, White, 1-Pin THD, RoHS, Bulk")
      (fields (field (name "MANUFACTURER") "KeystoneElectronics"))
      (libsource (lib "Altium Content Vault") (part "KSTN-TP-5002"))
    )
    (comp (ref "TP6")
      (value "5002")
      (footprint "KSTN-5002")
      (description "Test Point, White, 1-Pin THD, RoHS, Bulk")
      (fields (field (name "MANUFACTURER") "KeystoneElectronics"))
      (libsource (lib "Altium Content Vault") (part "KSTN-TP-5002"))
    )
    (comp (ref "TP7")
      (value "5002")
      (footprint "KSTN-5002")
      (description "Test Point, White, 1-Pin THD, RoHS, Bulk")
      (fields (field (name "MANUFACTURER") "KeystoneElectronics"))
      (libsource (lib "Altium Content Vault") (part "KSTN-TP-5002"))
    )
    (comp (ref "TP8")
      (value "5002")
      (footprint "KSTN-5002")
      (description "Test Point, White, 1-Pin THD, RoHS, Bulk")
      (fields (field (name "MANUFACTURER") "KeystoneElectronics"))
      (libsource (lib "Altium Content Vault") (part "KSTN-TP-5002"))
    )
    (comp (ref "TP9")
      (value "5002")
      (footprint "KSTN-5002")
      (description "Test Point, White, 1-Pin THD, RoHS, Bulk")
      (fields (field (name "MANUFACTURER") "KeystoneElectronics"))
      (libsource (lib "Altium Content Vault") (part "KSTN-TP-5002"))
    )
    (comp (ref "TP18")
      (value "5001")
      (footprint "KSTN-5001")
      (description "Test Point, Black, 1-Pin THD, RoHS, Bulk")
      (fields (field (name "MANUFACTURER") "Keystone"))
      (libsource (lib "Altium Content Vault") (part "KSTN-TP-5001"))
    )
    (comp (ref "TP19")
      (value "5002")
      (footprint "KSTN-5002")
      (description "Test Point, White, 1-Pin THD, RoHS, Bulk")
      (fields (field (name "MANUFACTURER") "KeystoneElectronics"))
      (libsource (lib "Altium Content Vault") (part "KSTN-TP-5002"))
    )
    (comp (ref "TP20")
      (value "5002")
      (footprint "KSTN-5002")
      (description "Test Point, White, 1-Pin THD, RoHS, Bulk")
      (fields (field (name "MANUFACTURER") "KeystoneElectronics"))
      (libsource (lib "Altium Content Vault") (part "KSTN-TP-5002"))
    )
    (comp (ref "TP21")
      (value "5002")
      (footprint "KSTN-5002")
      (description "Test Point, White, 1-Pin THD, RoHS, Bulk")
      (fields (field (name "MANUFACTURER") "KeystoneElectronics"))
      (libsource (lib "Altium Content Vault") (part "KSTN-TP-5002"))
    )
    (comp (ref "TP22")
      (value "5002")
      (footprint "KSTN-5002")
      (description "Test Point, White, 1-Pin THD, RoHS, Bulk")
      (fields (field (name "MANUFACTURER") "KeystoneElectronics"))
      (libsource (lib "Altium Content Vault") (part "KSTN-TP-5002"))
    )
    (comp (ref "TP23")
      (value "5002")
      (footprint "KSTN-5002")
      (description "Test Point, White, 1-Pin THD, RoHS, Bulk")
      (fields (field (name "MANUFACTURER") "KeystoneElectronics"))
      (libsource (lib "Altium Content Vault") (part "KSTN-TP-5002"))
    )
    (comp (ref "TP24")
      (value "5001")
      (footprint "KSTN-5001")
      (description "Test Point, Black, 1-Pin THD, RoHS, Bulk")
      (fields (field (name "MANUFACTURER") "Keystone"))
      (libsource (lib "Altium Content Vault") (part "KSTN-TP-5001"))
    )
    (comp (ref "TP25")
      (value "5002")
      (footprint "KSTN-5002")
      (description "Test Point, White, 1-Pin THD, RoHS, Bulk")
      (fields (field (name "MANUFACTURER") "KeystoneElectronics"))
      (libsource (lib "Altium Content Vault") (part "KSTN-TP-5002"))
    )
    (comp (ref "TP26")
      (value "5001")
      (footprint "KSTN-5001")
      (description "Test Point, Black, 1-Pin THD, RoHS, Bulk")
      (fields (field (name "MANUFACTURER") "Keystone"))
      (libsource (lib "Altium Content Vault") (part "KSTN-TP-5001"))
    )
    (comp (ref "TP27")
      (value "5002")
      (footprint "KSTN-5002")
      (description "Test Point, White, 1-Pin THD, RoHS, Bulk")
      (fields (field (name "MANUFACTURER") "KeystoneElectronics"))
      (libsource (lib "Altium Content Vault") (part "KSTN-TP-5002"))
    )
    (comp (ref "TP28")
      (value "5002")
      (footprint "KSTN-5002")
      (description "Test Point, White, 1-Pin THD, RoHS, Bulk")
      (fields (field (name "MANUFACTURER") "KeystoneElectronics"))
      (libsource (lib "Altium Content Vault") (part "KSTN-TP-5002"))
    )
    (comp (ref "TP29")
      (value "5001")
      (footprint "KSTN-5001")
      (description "Test Point, Black, 1-Pin THD, RoHS, Bulk")
      (fields (field (name "MANUFACTURER") "Keystone"))
      (libsource (lib "Altium Content Vault") (part "KSTN-TP-5001"))
    )
    (comp (ref "TP30")
      (value "5002")
      (footprint "KSTN-5002")
      (description "Test Point, White, 1-Pin THD, RoHS, Bulk")
      (fields (field (name "MANUFACTURER") "KeystoneElectronics"))
      (libsource (lib "Altium Content Vault") (part "KSTN-TP-5002"))
    )
    (comp (ref "TP31")
      (value "5002")
      (footprint "KSTN-5002")
      (description "Test Point, White, 1-Pin THD, RoHS, Bulk")
      (fields (field (name "MANUFACTURER") "KeystoneElectronics"))
      (libsource (lib "Altium Content Vault") (part "KSTN-TP-5002"))
    )
    (comp (ref "TP32")
      (value "5002")
      (footprint "KSTN-5002")
      (description "Test Point, White, 1-Pin THD, RoHS, Bulk")
      (fields (field (name "MANUFACTURER") "KeystoneElectronics"))
      (libsource (lib "Altium Content Vault") (part "KSTN-TP-5002"))
    )
    (comp (ref "TP33")
      (value "5002")
      (footprint "KSTN-5002")
      (description "Test Point, White, 1-Pin THD, RoHS, Bulk")
      (fields (field (name "MANUFACTURER") "KeystoneElectronics"))
      (libsource (lib "Altium Content Vault") (part "KSTN-TP-5002"))
    )
    (comp (ref "TP34")
      (value "5002")
      (footprint "KSTN-5002")
      (description "Test Point, White, 1-Pin THD, RoHS, Bulk")
      (fields (field (name "MANUFACTURER") "KeystoneElectronics"))
      (libsource (lib "Altium Content Vault") (part "KSTN-TP-5002"))
    )
    (comp (ref "TP35")
      (value "5002")
      (footprint "KSTN-5002")
      (description "Test Point, White, 1-Pin THD, RoHS, Bulk")
      (fields (field (name "MANUFACTURER") "KeystoneElectronics"))
      (libsource (lib "Altium Content Vault") (part "KSTN-TP-5002"))
    )
    (comp (ref "U1")
      (value "LM27762DSSR")
      (footprint "FP-DSS0012B-MFG")
      (description "IC REG CHARGE PUMP ADJ DL 12WSON")
      (libsource (lib "Altium Content Vault") (part "ab275a4f98ccada617dcf409ec46a20"))
    )
    (comp (ref "X1")
      (value "pga_socket_208_highspeed_cutout")
      (footprint "pga_socket_208pin_highspeed_cutout")
      (libsource (lib "pga_socket_square_208pin_17x17_minus_9x9") (part "pga_socket_208_highspeed_cutout"))
    )
  )
  (nets
    (net (code "1") (name "/AVDD_1V0") (class "Default")
      (node (ref "J3") (pin "1") (pinfunction "1_1") (pintype "passive"))
      (node (ref "J3") (pin "3") (pinfunction "3_3") (pintype "passive"))
    )
    (net (code "2") (name "/CNOT_PHASE_HEATP_1") (class "Default")
      (node (ref "J7") (pin "2") (pinfunction "2_2") (pintype "passive"))
      (node (ref "X1") (pin "B9") (pinfunction "B9_B9") (pintype "passive"))
    )
    (net (code "3") (name "/CNOT_PHASE_HEATP_2") (class "Default")
      (node (ref "J7") (pin "4") (pinfunction "4_4") (pintype "passive"))
      (node (ref "X1") (pin "B8") (pinfunction "B8_B8") (pintype "passive"))
    )
    (net (code "4") (name "/CNOT_PHASE_HEATP_3") (class "Default")
      (node (ref "J7") (pin "6") (pinfunction "6_6") (pintype "passive"))
      (node (ref "X1") (pin "A10") (pinfunction "A10_A10") (pintype "passive"))
    )
    (net (code "5") (name "/CNOT_PHASE_HEATP_4") (class "Default")
      (node (ref "J7") (pin "8") (pinfunction "8_8") (pintype "passive"))
      (node (ref "X1") (pin "B7") (pinfunction "B7_B7") (pintype "passive"))
    )
    (net (code "6") (name "/CNOT_PHASE_HEATP_5") (class "Default")
      (node (ref "J7") (pin "10") (pinfunction "10_10") (pintype "passive"))
      (node (ref "X1") (pin "B6") (pinfunction "B6_B6") (pintype "passive"))
    )
    (net (code "7") (name "/CP_EN_M") (class "Default")
      (node (ref "P2") (pin "2") (pinfunction "2_2") (pintype "passive"))
      (node (ref "R25") (pin "2") (pinfunction "2_2") (pintype "passive"))
      (node (ref "U1") (pin "8") (pinfunction "EN-_8") (pintype "input"))
    )
    (net (code "8") (name "/CP_EN_P") (class "Default")
      (node (ref "R27") (pin "1") (pinfunction "1_1") (pintype "passive"))
      (node (ref "U1") (pin "12") (pinfunction "EN+_12") (pintype "input"))
    )
    (net (code "9") (name "/CP_FB_M") (class "Default")
      (node (ref "R3") (pin "2") (pinfunction "WIPER_2") (pintype "passive"))
      (node (ref "R57") (pin "1") (pinfunction "1_1") (pintype "passive"))
      (node (ref "R58") (pin "2") (pinfunction "2_2") (pintype "passive"))
      (node (ref "U1") (pin "7") (pinfunction "FB-_7") (pintype "input"))
    )
    (net (code "10") (name "/CP_FB_P") (class "Default")
      (node (ref "R2") (pin "2") (pinfunction "WIPER_2") (pintype "passive"))
      (node (ref "R59") (pin "1") (pinfunction "1_1") (pintype "passive"))
      (node (ref "R60") (pin "2") (pinfunction "2_2") (pintype "passive"))
      (node (ref "U1") (pin "2") (pinfunction "FB+_2") (pintype "input"))
    )
    (net (code "11") (name "/CP_FLY_N") (class "Default")
      (node (ref "C12") (pin "2") (pinfunction "2_2") (pintype "passive"))
      (node (ref "U1") (pin "9") (pinfunction "C1-_9") (pintype "passive"))
    )
    (net (code "12") (name "/CP_FLY_P") (class "Default")
      (node (ref "C12") (pin "1") (pinfunction "1_1") (pintype "passive"))
      (node (ref "U1") (pin "10") (pinfunction "C1+_10") (pintype "passive"))
    )
    (net (code "13") (name "/CP_OUT_M") (class "Default")
      (node (ref "C7") (pin "1") (pinfunction "1_1") (pintype "passive"))
      (node (ref "C8") (pin "1") (pinfunction "1_1") (pintype "passive"))
      (node (ref "R29") (pin "1") (pinfunction "1_1") (pintype "passive"))
      (node (ref "R3") (pin "3") (pinfunction "CW_3") (pintype "passive"))
      (node (ref "R30") (pin "1") (pinfunction "1_1") (pintype "passive"))
      (node (ref "R57") (pin "2") (pinfunction "2_2") (pintype "passive"))
      (node (ref "TP7") (pin "1") (pintype "passive"))
      (node (ref "U1") (pin "6") (pinfunction "OUT-_6") (pintype "passive"))
    )
    (net (code "14") (name "/CP_OUT_P") (class "Default")
      (node (ref "R2") (pin "3") (pinfunction "CW_3") (pintype "passive"))
      (node (ref "R28") (pin "1") (pinfunction "1_1") (pintype "passive"))
      (node (ref "R59") (pin "2") (pinfunction "2_2") (pintype "passive"))
      (node (ref "TP6") (pin "1") (pintype "passive"))
      (node (ref "U1") (pin "11") (pinfunction "OUT+_11") (pintype "passive"))
    )
    (net (code "15") (name "/CP_PGOOD") (class "Default")
      (node (ref "R26") (pin "1") (pinfunction "1_1") (pintype "passive"))
      (node (ref "U1") (pin "1") (pinfunction "PGOOD_1") (pintype "open_collector"))
    )
    (net (code "16") (name "/CP_SW_OUT") (class "Default")
      (node (ref "C3") (pin "1") (pinfunction "1_1") (pintype "passive"))
      (node (ref "C5") (pin "1") (pinfunction "1_1") (pintype "passive"))
      (node (ref "U1") (pin "5") (pinfunction "CP_5") (pintype "passive"))
    )
    (net (code "17") (name "/DVDD_1V8") (class "Default")
      (node (ref "J5") (pin "1") (pinfunction "1_1") (pintype "passive"))
      (node (ref "J5") (pin "3") (pinfunction "3_3") (pintype "passive"))
    )
    (net (code "18") (name "/EOS26_DVDD_1V8") (class "Default")
      (node (ref "J5") (pin "4") (pinfunction "4_4") (pintype "passive"))
      (node (ref "X1") (pin "B2") (pinfunction "B2_B2") (pintype "passive"))
      (node (ref "X1") (pin "B4") (pinfunction "B4_B4") (pintype "passive"))
    )
    (net (code "19") (name "/EOS26_OVDD_1V0") (class "Default")
      (node (ref "J3") (pin "4") (pinfunction "4_4") (pintype "passive"))
      (node (ref "R36") (pin "2") (pinfunction "2_2") (pintype "passive"))
      (node (ref "R50") (pin "2") (pinfunction "2_2") (pintype "passive"))
      (node (ref "X1") (pin "C1") (pinfunction "C1_C1") (pintype "passive"))
      (node (ref "X1") (pin "C3") (pinfunction "C3_C3") (pintype "passive"))
      (node (ref "X1") (pin "C5") (pinfunction "C5_C5") (pintype "passive"))
    )
    (net (code "20") (name "/EOS26_VDD_1V0") (class "Default")
      (node (ref "J4") (pin "4") (pinfunction "4_4") (pintype "passive"))
      (node (ref "X1") (pin "A1") (pinfunction "A1_A1") (pintype "passive"))
      (node (ref "X1") (pin "A3") (pinfunction "A3_A3") (pintype "passive"))
    )
    (net (code "21") (name "/EOS34_AVDD_1V0") (class "Default")
      (node (ref "J3") (pin "2") (pinfunction "2_2") (pintype "passive"))
      (node (ref "R10") (pin "3") (pinfunction "CW_3") (pintype "passive"))
      (node (ref "R11") (pin "3") (pinfunction "CW_3") (pintype "passive"))
      (node (ref "R12") (pin "3") (pinfunction "CW_3") (pintype "passive"))
      (node (ref "R51") (pin "2") (pinfunction "2_2") (pintype "passive"))
      (node (ref "X1") (pin "P2") (pinfunction "P2_P2") (pintype "passive"))
      (node (ref "X1") (pin "P4") (pinfunction "P4_P4") (pintype "passive"))
    )
    (net (code "22") (name "/EOS34_DVDD_1V8") (class "Default")
      (node (ref "J5") (pin "2") (pinfunction "2_2") (pintype "passive"))
      (node (ref "X1") (pin "S2") (pinfunction "S2_S2") (pintype "passive"))
      (node (ref "X1") (pin "S4") (pinfunction "S4_S4") (pintype "passive"))
    )
    (net (code "23") (name "/EOS34_HVDD_2V5") (class "Default")
      (node (ref "X1") (pin "T1") (pinfunction "T1_T1") (pintype "passive"))
      (node (ref "X1") (pin "T3") (pinfunction "T3_T3") (pintype "passive"))
    )
    (net (code "24") (name "/EOS34_VDD_1V0") (class "Default")
      (node (ref "J4") (pin "2") (pinfunction "2_2") (pintype "passive"))
      (node (ref "R22") (pin "2") (pinfunction "2_2") (pintype "passive"))
      (node (ref "R23") (pin "2") (pinfunction "2_2") (pintype "passive"))
      (node (ref "R24") (pin "2") (pinfunction "2_2") (pintype "passive"))
      (node (ref "X1") (pin "R1") (pinfunction "R1_R1") (pintype "passive"))
      (node (ref "X1") (pin "R3") (pinfunction "R3_R3") (pintype "passive"))
    )
    (net (code "25") (name "/ICR_RING_HEATP_1") (class "Default")
      (node (ref "J6") (pin "10") (pinfunction "10_10") (pintype "passive"))
      (node (ref "X1") (pin "D12") (pinfunction "D12_D12") (pintype "passive"))
    )
    (net (code "26") (name "/ICR_RING_HEATP_2") (class "Default")
      (node (ref "J6") (pin "12") (pinfunction "12_12") (pintype "passive"))
      (node (ref "X1") (pin "D11") (pinfunction "D11_D11") (pintype "passive"))
    )
    (net (code "27") (name "/ICR_RING_HEATP_3") (class "Default")
      (node (ref "J6") (pin "14") (pinfunction "14_14") (pintype "passive"))
      (node (ref "X1") (pin "C7") (pinfunction "C7_C7") (pintype "passive"))
    )
    (net (code "28") (name "/ICR_RING_HEATP_4") (class "Default")
      (node (ref "J6") (pin "16") (pinfunction "16_16") (pintype "passive"))
      (node (ref "X1") (pin "C6") (pinfunction "C6_C6") (pintype "passive"))
    )
    (net (code "29") (name "/PES_PHASE_HEATP_1") (class "Default")
      (node (ref "J6") (pin "2") (pinfunction "2_2") (pintype "passive"))
      (node (ref "X1") (pin "A9") (pinfunction "A9_A9") (pintype "passive"))
    )
    (net (code "30") (name "/PES_PHASE_HEATP_2") (class "Default")
      (node (ref "J6") (pin "4") (pinfunction "4_4") (pintype "passive"))
      (node (ref "X1") (pin "A8") (pinfunction "A8_A8") (pintype "passive"))
    )
    (net (code "31") (name "/PES_PHASE_HEATP_3") (class "Default")
      (node (ref "J6") (pin "6") (pinfunction "6_6") (pintype "passive"))
      (node (ref "X1") (pin "A7") (pinfunction "A7_A7") (pintype "passive"))
    )
    (net (code "32") (name "/PES_PHASE_HEATP_4") (class "Default")
      (node (ref "J6") (pin "8") (pinfunction "8_8") (pintype "passive"))
      (node (ref "X1") (pin "A6") (pinfunction "A6_A6") (pintype "passive"))
    )
    (net (code "33") (name "/SFH_FILT_HEATP_1") (class "Default")
      (node (ref "J9") (pin "4") (pinfunction "4_4") (pintype "passive"))
      (node (ref "X1") (pin "B11") (pinfunction "B11_B11") (pintype "passive"))
    )
    (net (code "34") (name "/SFH_FILT_HEATP_2") (class "Default")
      (node (ref "J9") (pin "6") (pinfunction "6_6") (pintype "passive"))
      (node (ref "X1") (pin "C11") (pinfunction "C11_C11") (pintype "passive"))
    )
    (net (code "35") (name "/SFH_FILT_HEATP_3") (class "Default")
      (node (ref "J9") (pin "8") (pinfunction "8_8") (pintype "passive"))
      (node (ref "X1") (pin "C12") (pinfunction "C12_C12") (pintype "passive"))
    )
    (net (code "36") (name "/SFH_FILT_HEATP_4") (class "Default")
      (node (ref "J9") (pin "10") (pinfunction "10_10") (pintype "passive"))
      (node (ref "X1") (pin "B12") (pinfunction "B12_B12") (pintype "passive"))
    )
    (net (code "37") (name "/SFH_SOURCE_HEATP") (class "Default")
      (node (ref "J9") (pin "2") (pinfunction "2_2") (pintype "passive"))
      (node (ref "X1") (pin "A12") (pinfunction "A12_A12") (pintype "passive"))
    )
    (net (code "38") (name "/SWICR_PHASE_HEATP_1") (class "Default")
      (node (ref "J8") (pin "8") (pinfunction "8_8") (pintype "passive"))
      (node (ref "X1") (pin "D10") (pinfunction "D10_D10") (pintype "passive"))
    )
    (net (code "39") (name "/SWICR_PHASE_HEATP_2") (class "Default")
      (node (ref "J8") (pin "10") (pinfunction "10_10") (pintype "passive"))
      (node (ref "X1") (pin "C8") (pinfunction "C8_C8") (pintype "passive"))
    )
    (net (code "40") (name "/SWICR_PHASE_HEATP_3") (class "Default")
      (node (ref "J8") (pin "12") (pinfunction "12_12") (pintype "passive"))
      (node (ref "X1") (pin "D7") (pinfunction "D7_D7") (pintype "passive"))
    )
    (net (code "41") (name "/SWICR_RING_HEATP_1") (class "Default")
      (node (ref "J8") (pin "2") (pinfunction "2_2") (pintype "passive"))
      (node (ref "X1") (pin "B10") (pinfunction "B10_B10") (pintype "passive"))
    )
    (net (code "42") (name "/SWICR_RING_HEATP_2") (class "Default")
      (node (ref "J8") (pin "4") (pinfunction "4_4") (pintype "passive"))
      (node (ref "X1") (pin "C9") (pinfunction "C9_C9") (pintype "passive"))
    )
    (net (code "43") (name "/SWICR_RING_HEATP_3") (class "Default")
      (node (ref "J8") (pin "6") (pinfunction "6_6") (pintype "passive"))
      (node (ref "X1") (pin "D6") (pinfunction "D6_D6") (pintype "passive"))
    )
    (net (code "44") (name "/SWPS_PHASE_HEATP_1") (class "Default")
      (node (ref "J8") (pin "14") (pinfunction "14_14") (pintype "passive"))
      (node (ref "X1") (pin "D9") (pinfunction "D9_D9") (pintype "passive"))
    )
    (net (code "45") (name "/SWPS_PHASE_HEATP_2") (class "Default")
      (node (ref "J8") (pin "16") (pinfunction "16_16") (pintype "passive"))
      (node (ref "X1") (pin "D8") (pinfunction "D8_D8") (pintype "passive"))
    )
    (net (code "46") (name "/VDD_1V0") (class "Default")
      (node (ref "J4") (pin "1") (pinfunction "1_1") (pintype "passive"))
      (node (ref "J4") (pin "3") (pinfunction "3_3") (pintype "passive"))
    )
    (net (code "47") (name "/V_IN_PLUS_BANANA") (class "Default")
      (node (ref "C4") (pin "1") (pinfunction "1_1") (pintype "passive"))
      (node (ref "C6") (pin "1") (pinfunction "1_1") (pintype "passive"))
      (node (ref "J1") (pin "1") (pinfunction "1_1") (pintype "passive"))
      (node (ref "P1") (pin "2") (pinfunction "2_2") (pintype "passive"))
      (node (ref "P2") (pin "1") (pinfunction "1_1") (pintype "passive"))
      (node (ref "R26") (pin "2") (pinfunction "2_2") (pintype "passive"))
      (node (ref "R27") (pin "2") (pinfunction "2_2") (pintype "passive"))
      (node (ref "TP19") (pin "1") (pintype "passive"))
      (node (ref "U1") (pin "3") (pinfunction "VIN_3") (pintype "power_in"))
    )
    (net (code "48") (name "/eos26_ib_div") (class "Default")
      (node (ref "C27") (pin "1") (pinfunction "1_1") (pintype "passive"))
      (node (ref "C29") (pin "1") (pinfunction "1_1") (pintype "passive"))
      (node (ref "R63") (pin "2") (pinfunction "2_2") (pintype "passive"))
      (node (ref "TP3") (pin "1") (pintype "passive"))
      (node (ref "X1") (pin "D2") (pinfunction "D2_D2") (pintype "passive"))
    )
    (net (code "49") (name "/eos26_ib_div_shunt") (class "Default")
      (node (ref "R1") (pin "2") (pinfunction "WIPER_2") (pintype "passive"))
      (node (ref "R63") (pin "1") (pinfunction "1_1") (pintype "passive"))
      (node (ref "TP4") (pin "1") (pintype "passive"))
    )
    (net (code "50") (name "/eos26_ib_osc") (class "Default")
      (node (ref "C24") (pin "1") (pinfunction "1_1") (pintype "passive"))
      (node (ref "C25") (pin "1") (pinfunction "1_1") (pintype "passive"))
      (node (ref "R62") (pin "2") (pinfunction "2_2") (pintype "passive"))
      (node (ref "TP1") (pin "1") (pintype "passive"))
      (node (ref "X1") (pin "D4") (pinfunction "D4_D4") (pintype "passive"))
    )
    (net (code "51") (name "/eos26_ib_osc_shunt") (class "Default")
      (node (ref "R62") (pin "1") (pinfunction "1_1") (pintype "passive"))
      (node (ref "R9") (pin "2") (pinfunction "WIPER_2") (pintype "passive"))
      (node (ref "TP2") (pin "1") (pintype "passive"))
    )
    (net (code "52") (name "/eos26_mod_n") (class "Default")
      (node (ref "R30") (pin "2") (pinfunction "2_2") (pintype "passive"))
      (node (ref "X1") (pin "E1") (pinfunction "E1_E1") (pintype "passive"))
    )
    (net (code "53") (name "/eos26_mod_n_bl") (class "Default")
      (node (ref "R29") (pin "2") (pinfunction "2_2") (pintype "passive"))
      (node (ref "X1") (pin "E3") (pinfunction "E3_E3") (pintype "passive"))
    )
    (net (code "54") (name "/eos26_reset") (class "Default")
      (node (ref "J11") (pin "14") (pinfunction "14_14") (pintype "passive"))
      (node (ref "X1") (pin "E16") (pinfunction "E16_E16") (pintype "passive"))
    )
    (net (code "55") (name "/eos26_reset_async") (class "Default")
      (node (ref "J11") (pin "16") (pinfunction "16_16") (pintype "passive"))
      (node (ref "X1") (pin "E14") (pinfunction "E14_E14") (pintype "passive"))
    )
    (net (code "56") (name "/eos26_s_clk_n") (class "Default")
      (node (ref "J11") (pin "2") (pinfunction "2_2") (pintype "passive"))
      (node (ref "X1") (pin "C16") (pinfunction "C16_C16") (pintype "passive"))
    )
    (net (code "57") (name "/eos26_s_clk_p") (class "Default")
      (node (ref "J11") (pin "4") (pinfunction "4_4") (pintype "passive"))
      (node (ref "X1") (pin "C14") (pinfunction "C14_C14") (pintype "passive"))
    )
    (net (code "58") (name "/eos26_s_enable") (class "Default")
      (node (ref "J11") (pin "12") (pinfunction "12_12") (pintype "passive"))
      (node (ref "X1") (pin "A16") (pinfunction "A16_A16") (pintype "passive"))
    )
    (net (code "59") (name "/eos26_s_in") (class "Default")
      (node (ref "J11") (pin "6") (pinfunction "6_6") (pintype "passive"))
      (node (ref "X1") (pin "B15") (pinfunction "B15_B15") (pintype "passive"))
    )
    (net (code "60") (name "/eos26_s_out") (class "Default")
      (node (ref "J12") (pin "8") (pinfunction "8_8") (pintype "passive"))
      (node (ref "X1") (pin "A14") (pinfunction "A14_A14") (pintype "passive"))
    )
    (net (code "61") (name "/eos26_s_reset") (class "Default")
      (node (ref "J11") (pin "8") (pinfunction "8_8") (pintype "passive"))
      (node (ref "X1") (pin "B17") (pinfunction "B17_B17") (pintype "passive"))
    )
    (net (code "62") (name "/eos26_s_update") (class "Default")
      (node (ref "J11") (pin "10") (pinfunction "10_10") (pintype "passive"))
      (node (ref "X1") (pin "D17") (pinfunction "D17_D17") (pintype "passive"))
    )
    (net (code "63") (name "/eos34_IREF") (class "Default")
      (node (ref "C26") (pin "1") (pinfunction "1_1") (pintype "passive"))
      (node (ref "C28") (pin "1") (pinfunction "1_1") (pintype "passive"))
      (node (ref "R61") (pin "2") (pinfunction "2_2") (pintype "passive"))
      (node (ref "TP9") (pin "1") (pintype "passive"))
      (node (ref "X1") (pin "F2") (pinfunction "F2_F2") (pintype "passive"))
    )
    (net (code "64") (name "/eos34_IREF_shunt") (class "Default")
      (node (ref "R4") (pin "2") (pinfunction "WIPER_2") (pintype "passive"))
      (node (ref "R61") (pin "1") (pinfunction "1_1") (pintype "passive"))
      (node (ref "TP8") (pin "1") (pintype "passive"))
    )
    (net (code "65") (name "/eos34_MOD_HEAT") (class "Default")
      (node (ref "X1") (pin "J3") (pinfunction "J3_J3") (pintype "passive"))
    )
    (net (code "66") (name "/eos34_MOD_HV") (class "Default")
      (node (ref "X1") (pin "K4") (pinfunction "K4_K4") (pintype "passive"))
    )
    (net (code "67") (name "/eos34_PD_BIAS_N") (class "Default")
      (node (ref "X1") (pin "K2") (pinfunction "K2_K2") (pintype "passive"))
    )
    (net (code "68") (name "/eos34_PD_BIAS_P") (class "Default")
      (node (ref "X1") (pin "L1") (pinfunction "L1_L1") (pintype "passive"))
    )
    (net (code "69") (name "/eos34_PS_HEAT") (class "Default")
      (node (ref "X1") (pin "J1") (pinfunction "J1_J1") (pintype "passive"))
    )
    (net (code "70") (name "/eos34_TESTVD") (class "Default")
      (node (ref "TP23") (pin "1") (pintype "passive"))
      (node (ref "X1") (pin "H4") (pinfunction "H4_H4") (pintype "passive"))
    )
    (net (code "71") (name "/eos34_TESTVG") (class "Default")
      (node (ref "TP22") (pin "1") (pintype "passive"))
      (node (ref "X1") (pin "H2") (pinfunction "H2_H2") (pintype "passive"))
    )
    (net (code "72") (name "/eos34_TIE_HI") (class "Default")
      (node (ref "TP28") (pin "1") (pintype "passive"))
      (node (ref "X1") (pin "K15") (pinfunction "K15_K15") (pintype "passive"))
    )
    (net (code "73") (name "/eos34_TIE_LO") (class "Default")
      (node (ref "TP27") (pin "1") (pintype "passive"))
      (node (ref "X1") (pin "K17") (pinfunction "K17_K17") (pintype "passive"))
    )
    (net (code "74") (name "/eos34_VB_RING") (class "Default")
      (node (ref "X1") (pin "L3") (pinfunction "L3_L3") (pintype "passive"))
    )
    (net (code "75") (name "/eos34_VPD") (class "Default")
      (node (ref "C13") (pin "1") (pinfunction "1_1") (pintype "passive"))
      (node (ref "C9") (pin "1") (pinfunction "1_1") (pintype "passive"))
      (node (ref "R28") (pin "2") (pinfunction "2_2") (pintype "passive"))
      (node (ref "TP5") (pin "1") (pintype "passive"))
      (node (ref "X1") (pin "M4") (pinfunction "M4_M4") (pintype "passive"))
    )
    (net (code "76") (name "/eos34_VREF0") (class "Default")
      (node (ref "C16") (pin "1") (pinfunction "1_1") (pintype "passive"))
      (node (ref "C21") (pin "1") (pinfunction "1_1") (pintype "passive"))
      (node (ref "R12") (pin "2") (pinfunction "WIPER_2") (pintype "passive"))
      (node (ref "TP20") (pin "1") (pintype "passive"))
      (node (ref "X1") (pin "N1") (pinfunction "N1_N1") (pintype "passive"))
    )
    (net (code "77") (name "/eos34_VREF1") (class "Default")
      (node (ref "C15") (pin "1") (pinfunction "1_1") (pintype "passive"))
      (node (ref "C20") (pin "1") (pinfunction "1_1") (pintype "passive"))
      (node (ref "R11") (pin "2") (pinfunction "WIPER_2") (pintype "passive"))
      (node (ref "TP21") (pin "1") (pintype "passive"))
      (node (ref "X1") (pin "N3") (pinfunction "N3_N3") (pintype "passive"))
    )
    (net (code "78") (name "/eos34_VREF2") (class "Default")
      (node (ref "C14") (pin "1") (pinfunction "1_1") (pintype "passive"))
      (node (ref "C19") (pin "1") (pinfunction "1_1") (pintype "passive"))
      (node (ref "R10") (pin "2") (pinfunction "WIPER_2") (pintype "passive"))
      (node (ref "TP25") (pin "1") (pintype "passive"))
      (node (ref "X1") (pin "M2") (pinfunction "M2_M2") (pintype "passive"))
    )
    (net (code "79") (name "/eos34_VTERM") (class "Default")
      (node (ref "X1") (pin "F4") (pinfunction "F4_F4") (pintype "passive"))
    )
    (net (code "80") (name "/eos34_equip_reset") (class "Default")
      (node (ref "J12") (pin "16") (pinfunction "16_16") (pintype "passive"))
      (node (ref "X1") (pin "H15") (pinfunction "H15_H15") (pintype "passive"))
    )
    (net (code "81") (name "/eos34_hs_clk_ibias") (class "Default")
      (node (ref "C1") (pin "1") (pinfunction "1_1") (pintype "passive"))
      (node (ref "C2") (pin "1") (pinfunction "1_1") (pintype "passive"))
      (node (ref "R16") (pin "2") (pinfunction "2_2") (pintype "passive"))
      (node (ref "TP30") (pin "1") (pintype "passive"))
      (node (ref "X1") (pin "T14") (pinfunction "T14_T14") (pintype "passive"))
    )
    (net (code "82") (name "/eos34_hs_clk_ibias_shunt") (class "Default")
      (node (ref "R13") (pin "2") (pinfunction "WIPER_2") (pintype "passive"))
      (node (ref "R16") (pin "1") (pinfunction "1_1") (pintype "passive"))
      (node (ref "TP35") (pin "1") (pintype "passive"))
    )
    (net (code "83") (name "/eos34_ibias_rx_1") (class "Default")
      (node (ref "C17") (pin "1") (pinfunction "1_1") (pintype "passive"))
      (node (ref "C18") (pin "1") (pinfunction "1_1") (pintype "passive"))
      (node (ref "R17") (pin "2") (pinfunction "2_2") (pintype "passive"))
      (node (ref "TP31") (pin "1") (pintype "passive"))
      (node (ref "X1") (pin "G1") (pinfunction "G1_G1") (pintype "passive"))
    )
    (net (code "84") (name "/eos34_ibias_rx_1_shunt") (class "Default")
      (node (ref "R14") (pin "2") (pinfunction "WIPER_2") (pintype "passive"))
      (node (ref "R17") (pin "1") (pinfunction "1_1") (pintype "passive"))
      (node (ref "TP32") (pin "1") (pintype "passive"))
    )
    (net (code "85") (name "/eos34_ibias_rx_2") (class "Default")
      (node (ref "C10") (pin "1") (pinfunction "1_1") (pintype "passive"))
      (node (ref "C11") (pin "1") (pinfunction "1_1") (pintype "passive"))
      (node (ref "R18") (pin "2") (pinfunction "2_2") (pintype "passive"))
      (node (ref "TP33") (pin "1") (pintype "passive"))
      (node (ref "X1") (pin "G3") (pinfunction "G3_G3") (pintype "passive"))
    )
    (net (code "86") (name "/eos34_ibias_rx_2_shunt") (class "Default")
      (node (ref "R15") (pin "2") (pinfunction "WIPER_2") (pintype "passive"))
      (node (ref "R18") (pin "1") (pinfunction "1_1") (pintype "passive"))
      (node (ref "TP34") (pin "1") (pintype "passive"))
    )
    (net (code "87") (name "/eos34_rx_reset") (class "Default")
      (node (ref "J12") (pin "12") (pinfunction "12_12") (pintype "passive"))
      (node (ref "X1") (pin "J16") (pinfunction "J16_J16") (pintype "passive"))
    )
    (net (code "88") (name "/eos34_rx_reset_async") (class "Default")
      (node (ref "J12") (pin "14") (pinfunction "14_14") (pintype "passive"))
      (node (ref "X1") (pin "J14") (pinfunction "J14_J14") (pintype "passive"))
    )
    (net (code "89") (name "/eos34_s_clk_n") (class "Default")
      (node (ref "J10") (pin "2") (pinfunction "2_2") (pintype "passive"))
      (node (ref "X1") (pin "R16") (pinfunction "R16_R16") (pintype "passive"))
    )
    (net (code "90") (name "/eos34_s_clk_p") (class "Default")
      (node (ref "J10") (pin "4") (pinfunction "4_4") (pintype "passive"))
      (node (ref "X1") (pin "R14") (pinfunction "R14_R14") (pintype "passive"))
    )
    (net (code "91") (name "/eos34_s_enable_equip") (class "Default")
      (node (ref "J10") (pin "16") (pinfunction "16_16") (pintype "passive"))
      (node (ref "X1") (pin "L16") (pinfunction "L16_L16") (pintype "passive"))
    )
    (net (code "92") (name "/eos34_s_enable_rx") (class "Default")
      (node (ref "J10") (pin "14") (pinfunction "14_14") (pintype "passive"))
      (node (ref "X1") (pin "M17") (pinfunction "M17_M17") (pintype "passive"))
    )
    (net (code "93") (name "/eos34_s_enable_tx") (class "Default")
      (node (ref "J10") (pin "12") (pinfunction "12_12") (pintype "passive"))
      (node (ref "X1") (pin "N16") (pinfunction "N16_N16") (pintype "passive"))
    )
    (net (code "94") (name "/eos34_s_in") (class "Default")
      (node (ref "J10") (pin "6") (pinfunction "6_6") (pintype "passive"))
      (node (ref "X1") (pin "P15") (pinfunction "P15_P15") (pintype "passive"))
    )
    (net (code "95") (name "/eos34_s_out_equip") (class "Default")
      (node (ref "J12") (pin "6") (pinfunction "6_6") (pintype "passive"))
      (node (ref "X1") (pin "L14") (pinfunction "L14_L14") (pintype "passive"))
    )
    (net (code "96") (name "/eos34_s_out_rx") (class "Default")
      (node (ref "J12") (pin "4") (pinfunction "4_4") (pintype "passive"))
      (node (ref "X1") (pin "M15") (pinfunction "M15_M15") (pintype "passive"))
    )
    (net (code "97") (name "/eos34_s_out_tx") (class "Default")
      (node (ref "J12") (pin "2") (pinfunction "2_2") (pintype "passive"))
      (node (ref "X1") (pin "N14") (pinfunction "N14_N14") (pintype "passive"))
    )
    (net (code "98") (name "/eos34_s_reset") (class "Default")
      (node (ref "J10") (pin "8") (pinfunction "8_8") (pintype "passive"))
      (node (ref "X1") (pin "P17") (pinfunction "P17_P17") (pintype "passive"))
    )
    (net (code "99") (name "/eos34_s_update") (class "Default")
      (node (ref "J10") (pin "10") (pinfunction "10_10") (pintype "passive"))
      (node (ref "X1") (pin "S17") (pinfunction "S17_S17") (pintype "passive"))
    )
    (net (code "100") (name "GND") (class "Default")
      (node (ref "C1") (pin "2") (pinfunction "2_2") (pintype "passive"))
      (node (ref "C10") (pin "2") (pinfunction "2_2") (pintype "passive"))
      (node (ref "C11") (pin "2") (pinfunction "2_2") (pintype "passive"))
      (node (ref "C13") (pin "2") (pinfunction "2_2") (pintype "passive"))
      (node (ref "C14") (pin "2") (pinfunction "2_2") (pintype "passive"))
      (node (ref "C15") (pin "2") (pinfunction "2_2") (pintype "passive"))
      (node (ref "C16") (pin "2") (pinfunction "2_2") (pintype "passive"))
      (node (ref "C17") (pin "2") (pinfunction "2_2") (pintype "passive"))
      (node (ref "C18") (pin "2") (pinfunction "2_2") (pintype "passive"))
      (node (ref "C19") (pin "2") (pinfunction "2_2") (pintype "passive"))
      (node (ref "C2") (pin "2") (pinfunction "2_2") (pintype "passive"))
      (node (ref "C20") (pin "2") (pinfunction "2_2") (pintype "passive"))
      (node (ref "C21") (pin "2") (pinfunction "2_2") (pintype "passive"))
      (node (ref "C24") (pin "2") (pinfunction "2_2") (pintype "passive"))
      (node (ref "C25") (pin "2") (pinfunction "2_2") (pintype "passive"))
      (node (ref "C26") (pin "2") (pinfunction "2_2") (pintype "passive"))
      (node (ref "C27") (pin "2") (pinfunction "2_2") (pintype "passive"))
      (node (ref "C28") (pin "2") (pinfunction "2_2") (pintype "passive"))
      (node (ref "C29") (pin "2") (pinfunction "2_2") (pintype "passive"))
      (node (ref "C3") (pin "2") (pinfunction "2_2") (pintype "passive"))
      (node (ref "C4") (pin "2") (pinfunction "2_2") (pintype "passive"))
      (node (ref "C5") (pin "2") (pinfunction "2_2") (pintype "passive"))
      (node (ref "C6") (pin "2") (pinfunction "2_2") (pintype "passive"))
      (node (ref "C7") (pin "2") (pinfunction "2_2") (pintype "passive"))
      (node (ref "C8") (pin "2") (pinfunction "2_2") (pintype "passive"))
      (node (ref "C9") (pin "2") (pinfunction "2_2") (pintype "passive"))
      (node (ref "J10") (pin "1") (pinfunction "1_1") (pintype "passive"))
      (node (ref "J10") (pin "11") (pinfunction "11_11") (pintype "passive"))
      (node (ref "J10") (pin "13") (pinfunction "13_13") (pintype "passive"))
      (node (ref "J10") (pin "15") (pinfunction "15_15") (pintype "passive"))
      (node (ref "J10") (pin "3") (pinfunction "3_3") (pintype "passive"))
      (node (ref "J10") (pin "5") (pinfunction "5_5") (pintype "passive"))
      (node (ref "J10") (pin "7") (pinfunction "7_7") (pintype "passive"))
      (node (ref "J10") (pin "9") (pinfunction "9_9") (pintype "passive"))
      (node (ref "J11") (pin "1") (pinfunction "1_1") (pintype "passive"))
      (node (ref "J11") (pin "11") (pinfunction "11_11") (pintype "passive"))
      (node (ref "J11") (pin "13") (pinfunction "13_13") (pintype "passive"))
      (node (ref "J11") (pin "15") (pinfunction "15_15") (pintype "passive"))
      (node (ref "J11") (pin "3") (pinfunction "3_3") (pintype "passive"))
      (node (ref "J11") (pin "5") (pinfunction "5_5") (pintype "passive"))
      (node (ref "J11") (pin "7") (pinfunction "7_7") (pintype "passive"))
      (node (ref "J11") (pin "9") (pinfunction "9_9") (pintype "passive"))
      (node (ref "J12") (pin "1") (pinfunction "1_1") (pintype "passive"))
      (node (ref "J12") (pin "11") (pinfunction "11_11") (pintype "passive"))
      (node (ref "J12") (pin "13") (pinfunction "13_13") (pintype "passive"))
      (node (ref "J12") (pin "15") (pinfunction "15_15") (pintype "passive"))
      (node (ref "J12") (pin "3") (pinfunction "3_3") (pintype "passive"))
      (node (ref "J12") (pin "5") (pinfunction "5_5") (pintype "passive"))
      (node (ref "J12") (pin "7") (pinfunction "7_7") (pintype "passive"))
      (node (ref "J12") (pin "9") (pinfunction "9_9") (pintype "passive"))
      (node (ref "J2") (pin "1") (pinfunction "1_1") (pintype "passive"))
      (node (ref "J6") (pin "1") (pinfunction "1_1") (pintype "passive"))
      (node (ref "J6") (pin "11") (pinfunction "11_11") (pintype "passive"))
      (node (ref "J6") (pin "13") (pinfunction "13_13") (pintype "passive"))
      (node (ref "J6") (pin "15") (pinfunction "15_15") (pintype "passive"))
      (node (ref "J6") (pin "3") (pinfunction "3_3") (pintype "passive"))
      (node (ref "J6") (pin "5") (pinfunction "5_5") (pintype "passive"))
      (node (ref "J6") (pin "7") (pinfunction "7_7") (pintype "passive"))
      (node (ref "J6") (pin "9") (pinfunction "9_9") (pintype "passive"))
      (node (ref "J7") (pin "1") (pinfunction "1_1") (pintype "passive"))
      (node (ref "J7") (pin "11") (pinfunction "11_11") (pintype "passive"))
      (node (ref "J7") (pin "12") (pinfunction "12_12") (pintype "passive"))
      (node (ref "J7") (pin "13") (pinfunction "13_13") (pintype "passive"))
      (node (ref "J7") (pin "14") (pinfunction "14_14") (pintype "passive"))
      (node (ref "J7") (pin "15") (pinfunction "15_15") (pintype "passive"))
      (node (ref "J7") (pin "16") (pinfunction "16_16") (pintype "passive"))
      (node (ref "J7") (pin "3") (pinfunction "3_3") (pintype "passive"))
      (node (ref "J7") (pin "5") (pinfunction "5_5") (pintype "passive"))
      (node (ref "J7") (pin "7") (pinfunction "7_7") (pintype "passive"))
      (node (ref "J7") (pin "9") (pinfunction "9_9") (pintype "passive"))
      (node (ref "J8") (pin "1") (pinfunction "1_1") (pintype "passive"))
      (node (ref "J8") (pin "11") (pinfunction "11_11") (pintype "passive"))
      (node (ref "J8") (pin "13") (pinfunction "13_13") (pintype "passive"))
      (node (ref "J8") (pin "15") (pinfunction "15_15") (pintype "passive"))
      (node (ref "J8") (pin "3") (pinfunction "3_3") (pintype "passive"))
      (node (ref "J8") (pin "5") (pinfunction "5_5") (pintype "passive"))
      (node (ref "J8") (pin "7") (pinfunction "7_7") (pintype "passive"))
      (node (ref "J8") (pin "9") (pinfunction "9_9") (pintype "passive"))
      (node (ref "J9") (pin "1") (pinfunction "1_1") (pintype "passive"))
      (node (ref "J9") (pin "11") (pinfunction "11_11") (pintype "passive"))
      (node (ref "J9") (pin "12") (pinfunction "12_12") (pintype "passive"))
      (node (ref "J9") (pin "13") (pinfunction "13_13") (pintype "passive"))
      (node (ref "J9") (pin "14") (pinfunction "14_14") (pintype "passive"))
      (node (ref "J9") (pin "15") (pinfunction "15_15") (pintype "passive"))
      (node (ref "J9") (pin "16") (pinfunction "16_16") (pintype "passive"))
      (node (ref "J9") (pin "3") (pinfunction "3_3") (pintype "passive"))
      (node (ref "J9") (pin "5") (pinfunction "5_5") (pintype "passive"))
      (node (ref "J9") (pin "7") (pinfunction "7_7") (pintype "passive"))
      (node (ref "J9") (pin "9") (pinfunction "9_9") (pintype "passive"))
      (node (ref "P1") (pin "1") (pinfunction "1_1") (pintype "passive"))
      (node (ref "R10") (pin "1") (pinfunction "CCW_1") (pintype "passive"))
      (node (ref "R11") (pin "1") (pinfunction "CCW_1") (pintype "passive"))
      (node (ref "R12") (pin "1") (pinfunction "CCW_1") (pintype "passive"))
      (node (ref "R19") (pin "1") (pinfunction "1_1") (pintype "passive"))
      (node (ref "R2") (pin "1") (pinfunction "CCW_1") (pintype "passive"))
      (node (ref "R20") (pin "1") (pinfunction "1_1") (pintype "passive"))
      (node (ref "R21") (pin "1") (pinfunction "1_1") (pintype "passive"))
      (node (ref "R25") (pin "1") (pinfunction "1_1") (pintype "passive"))
      (node (ref "R3") (pin "1") (pinfunction "CCW_1") (pintype "passive"))
      (node (ref "R37") (pin "1") (pinfunction "1_1") (pintype "passive"))
      (node (ref "R52") (pin "1") (pinfunction "1_1") (pintype "passive"))
      (node (ref "R53") (pin "1") (pinfunction "1_1") (pintype "passive"))
      (node (ref "R58") (pin "1") (pinfunction "1_1") (pintype "passive"))
      (node (ref "R60") (pin "1") (pinfunction "1_1") (pintype "passive"))
      (node (ref "TP18") (pin "1") (pintype "passive"))
      (node (ref "TP24") (pin "1") (pintype "passive"))
      (node (ref "TP26") (pin "1") (pintype "passive"))
      (node (ref "TP29") (pin "1") (pintype "passive"))
      (node (ref "U1") (pin "13") (pinfunction "Thermal_Pad_13") (pintype "passive"))
      (node (ref "U1") (pin "4") (pinfunction "GND_4") (pintype "power_in"))
      (node (ref "X1") (pin "A11") (pinfunction "A11_A11") (pintype "passive"))
      (node (ref "X1") (pin "A13") (pinfunction "A13_A13") (pintype "passive"))
      (node (ref "X1") (pin "A15") (pinfunction "A15_A15") (pintype "passive"))
      (node (ref "X1") (pin "A17") (pinfunction "A17_A17") (pintype "passive"))
      (node (ref "X1") (pin "A2") (pinfunction "A2_A2") (pintype "passive"))
      (node (ref "X1") (pin "A4") (pinfunction "A4_A4") (pintype "passive"))
      (node (ref "X1") (pin "A5") (pinfunction "A5_A5") (pintype "passive"))
      (node (ref "X1") (pin "B1") (pinfunction "B1_B1") (pintype "passive"))
      (node (ref "X1") (pin "B13") (pinfunction "B13_B13") (pintype "passive"))
      (node (ref "X1") (pin "B14") (pinfunction "B14_B14") (pintype "passive"))
      (node (ref "X1") (pin "B16") (pinfunction "B16_B16") (pintype "passive"))
      (node (ref "X1") (pin "B3") (pinfunction "B3_B3") (pintype "passive"))
      (node (ref "X1") (pin "B5") (pinfunction "B5_B5") (pintype "passive"))
      (node (ref "X1") (pin "C10") (pinfunction "C10_C10") (pintype "passive"))
      (node (ref "X1") (pin "C13") (pinfunction "C13_C13") (pintype "passive"))
      (node (ref "X1") (pin "C15") (pinfunction "C15_C15") (pintype "passive"))
      (node (ref "X1") (pin "C17") (pinfunction "C17_C17") (pintype "passive"))
      (node (ref "X1") (pin "C2") (pinfunction "C2_C2") (pintype "passive"))
      (node (ref "X1") (pin "C4") (pinfunction "C4_C4") (pintype "passive"))
      (node (ref "X1") (pin "D1") (pinfunction "D1_D1") (pintype "passive"))
      (node (ref "X1") (pin "D13") (pinfunction "D13_D13") (pintype "passive"))
      (node (ref "X1") (pin "D14") (pinfunction "D14_D14") (pintype "passive"))
      (node (ref "X1") (pin "D15") (pinfunction "D15_D15") (pintype "passive"))
      (node (ref "X1") (pin "D16") (pinfunction "D16_D16") (pintype "passive"))
      (node (ref "X1") (pin "D3") (pinfunction "D3_D3") (pintype "passive"))
      (node (ref "X1") (pin "D5") (pinfunction "D5_D5") (pintype "passive"))
      (node (ref "X1") (pin "E15") (pinfunction "E15_E15") (pintype "passive"))
      (node (ref "X1") (pin "E17") (pinfunction "E17_E17") (pintype "passive"))
      (node (ref "X1") (pin "E2") (pinfunction "E2_E2") (pintype "passive"))
      (node (ref "X1") (pin "E4") (pinfunction "E4_E4") (pintype "passive"))
      (node (ref "X1") (pin "F1") (pinfunction "F1_F1") (pintype "passive"))
      (node (ref "X1") (pin "F14") (pinfunction "F14_F14") (pintype "passive"))
      (node (ref "X1") (pin "F15") (pinfunction "F15_F15") (pintype "passive"))
      (node (ref "X1") (pin "F16") (pinfunction "F16_F16") (pintype "passive"))
      (node (ref "X1") (pin "F17") (pinfunction "F17_F17") (pintype "passive"))
      (node (ref "X1") (pin "F3") (pinfunction "F3_F3") (pintype "passive"))
      (node (ref "X1") (pin "G14") (pinfunction "G14_G14") (pintype "passive"))
      (node (ref "X1") (pin "G15") (pinfunction "G15_G15") (pintype "passive"))
      (node (ref "X1") (pin "G16") (pinfunction "G16_G16") (pintype "passive"))
      (node (ref "X1") (pin "G17") (pinfunction "G17_G17") (pintype "passive"))
      (node (ref "X1") (pin "G2") (pinfunction "G2_G2") (pintype "passive"))
      (node (ref "X1") (pin "G4") (pinfunction "G4_G4") (pintype "passive"))
      (node (ref "X1") (pin "H1") (pinfunction "H1_H1") (pintype "passive"))
      (node (ref "X1") (pin "H14") (pinfunction "H14_H14") (pintype "passive"))
      (node (ref "X1") (pin "H16") (pinfunction "H16_H16") (pintype "passive"))
      (node (ref "X1") (pin "H17") (pinfunction "H17_H17") (pintype "passive"))
      (node (ref "X1") (pin "H3") (pinfunction "H3_H3") (pintype "passive"))
      (node (ref "X1") (pin "J15") (pinfunction "J15_J15") (pintype "passive"))
      (node (ref "X1") (pin "J17") (pinfunction "J17_J17") (pintype "passive"))
      (node (ref "X1") (pin "J2") (pinfunction "J2_J2") (pintype "passive"))
      (node (ref "X1") (pin "J4") (pinfunction "J4_J4") (pintype "passive"))
      (node (ref "X1") (pin "K1") (pinfunction "K1_K1") (pintype "passive"))
      (node (ref "X1") (pin "K14") (pinfunction "K14_K14") (pintype "passive"))
      (node (ref "X1") (pin "K16") (pinfunction "K16_K16") (pintype "passive"))
      (node (ref "X1") (pin "K3") (pinfunction "K3_K3") (pintype "passive"))
      (node (ref "X1") (pin "L15") (pinfunction "L15_L15") (pintype "passive"))
      (node (ref "X1") (pin "L17") (pinfunction "L17_L17") (pintype "passive"))
      (node (ref "X1") (pin "L2") (pinfunction "L2_L2") (pintype "passive"))
      (node (ref "X1") (pin "L4") (pinfunction "L4_L4") (pintype "passive"))
      (node (ref "X1") (pin "M1") (pinfunction "M1_M1") (pintype "passive"))
      (node (ref "X1") (pin "M14") (pinfunction "M14_M14") (pintype "passive"))
      (node (ref "X1") (pin "M16") (pinfunction "M16_M16") (pintype "passive"))
      (node (ref "X1") (pin "M3") (pinfunction "M3_M3") (pintype "passive"))
      (node (ref "X1") (pin "N15") (pinfunction "N15_N15") (pintype "passive"))
      (node (ref "X1") (pin "N17") (pinfunction "N17_N17") (pintype "passive"))
      (node (ref "X1") (pin "N2") (pinfunction "N2_N2") (pintype "passive"))
      (node (ref "X1") (pin "N4") (pinfunction "N4_N4") (pintype "passive"))
      (node (ref "X1") (pin "P1") (pinfunction "P1_P1") (pintype "passive"))
      (node (ref "X1") (pin "P14") (pinfunction "P14_P14") (pintype "passive"))
      (node (ref "X1") (pin "P16") (pinfunction "P16_P16") (pintype "passive"))
      (node (ref "X1") (pin "P3") (pinfunction "P3_P3") (pintype "passive"))
      (node (ref "X1") (pin "R15") (pinfunction "R15_R15") (pintype "passive"))
      (node (ref "X1") (pin "R17") (pinfunction "R17_R17") (pintype "passive"))
      (node (ref "X1") (pin "R2") (pinfunction "R2_R2") (pintype "passive"))
      (node (ref "X1") (pin "R4") (pinfunction "R4_R4") (pintype "passive"))
      (node (ref "X1") (pin "S1") (pinfunction "S1_S1") (pintype "passive"))
      (node (ref "X1") (pin "S14") (pinfunction "S14_S14") (pintype "passive"))
      (node (ref "X1") (pin "S15") (pinfunction "S15_S15") (pintype "passive"))
      (node (ref "X1") (pin "S16") (pinfunction "S16_S16") (pintype "passive"))
      (node (ref "X1") (pin "S3") (pinfunction "S3_S3") (pintype "passive"))
      (node (ref "X1") (pin "T15") (pinfunction "T15_T15") (pintype "passive"))
      (node (ref "X1") (pin "T16") (pinfunction "T16_T16") (pintype "passive"))
      (node (ref "X1") (pin "T17") (pinfunction "T17_T17") (pintype "passive"))
      (node (ref "X1") (pin "T2") (pinfunction "T2_T2") (pintype "passive"))
      (node (ref "X1") (pin "T4") (pinfunction "T4_T4") (pintype "passive"))
    )
    (net (code "101") (name "Net-(R1-CCW)") (class "Default")
      (node (ref "R1") (pin "1") (pinfunction "CCW_1") (pintype "passive"))
      (node (ref "R50") (pin "1") (pinfunction "1_1") (pintype "passive"))
    )
    (net (code "102") (name "Net-(R1-CW)") (class "Default")
      (node (ref "R1") (pin "3") (pinfunction "CW_3") (pintype "passive"))
      (node (ref "R52") (pin "2") (pinfunction "2_2") (pintype "passive"))
    )
    (net (code "103") (name "Net-(R4-CCW)") (class "Default")
      (node (ref "R4") (pin "1") (pinfunction "CCW_1") (pintype "passive"))
      (node (ref "R51") (pin "1") (pinfunction "1_1") (pintype "passive"))
    )
    (net (code "104") (name "Net-(R4-CW)") (class "Default")
      (node (ref "R4") (pin "3") (pinfunction "CW_3") (pintype "passive"))
      (node (ref "R53") (pin "2") (pinfunction "2_2") (pintype "passive"))
    )
    (net (code "105") (name "Net-(R9-CCW)") (class "Default")
      (node (ref "R36") (pin "1") (pinfunction "1_1") (pintype "passive"))
      (node (ref "R9") (pin "1") (pinfunction "CCW_1") (pintype "passive"))
    )
    (net (code "106") (name "Net-(R9-CW)") (class "Default")
      (node (ref "R37") (pin "2") (pinfunction "2_2") (pintype "passive"))
      (node (ref "R9") (pin "3") (pinfunction "CW_3") (pintype "passive"))
    )
    (net (code "107") (name "Net-(R13-CCW)") (class "Default")
      (node (ref "R13") (pin "1") (pinfunction "CCW_1") (pintype "passive"))
      (node (ref "R22") (pin "1") (pinfunction "1_1") (pintype "passive"))
    )
    (net (code "108") (name "Net-(R13-CW)") (class "Default")
      (node (ref "R13") (pin "3") (pinfunction "CW_3") (pintype "passive"))
      (node (ref "R19") (pin "2") (pinfunction "2_2") (pintype "passive"))
    )
    (net (code "109") (name "Net-(R14-CCW)") (class "Default")
      (node (ref "R14") (pin "1") (pinfunction "CCW_1") (pintype "passive"))
      (node (ref "R23") (pin "1") (pinfunction "1_1") (pintype "passive"))
    )
    (net (code "110") (name "Net-(R14-CW)") (class "Default")
      (node (ref "R14") (pin "3") (pinfunction "CW_3") (pintype "passive"))
      (node (ref "R20") (pin "2") (pinfunction "2_2") (pintype "passive"))
    )
    (net (code "111") (name "Net-(R15-CCW)") (class "Default")
      (node (ref "R15") (pin "1") (pinfunction "CCW_1") (pintype "passive"))
      (node (ref "R24") (pin "1") (pinfunction "1_1") (pintype "passive"))
    )
    (net (code "112") (name "Net-(R15-CW)") (class "Default")
      (node (ref "R15") (pin "3") (pinfunction "CW_3") (pintype "passive"))
      (node (ref "R21") (pin "2") (pinfunction "2_2") (pintype "passive"))
    )
    (net (code "113") (name "unconnected-(J12-Pad10)") (class "Default")
      (node (ref "J12") (pin "10") (pinfunction "10_10") (pintype "passive"))
    )
  )
)
